# rev_p_2-v18.net
KiCad netlist of a schematic drawn in EAGLE
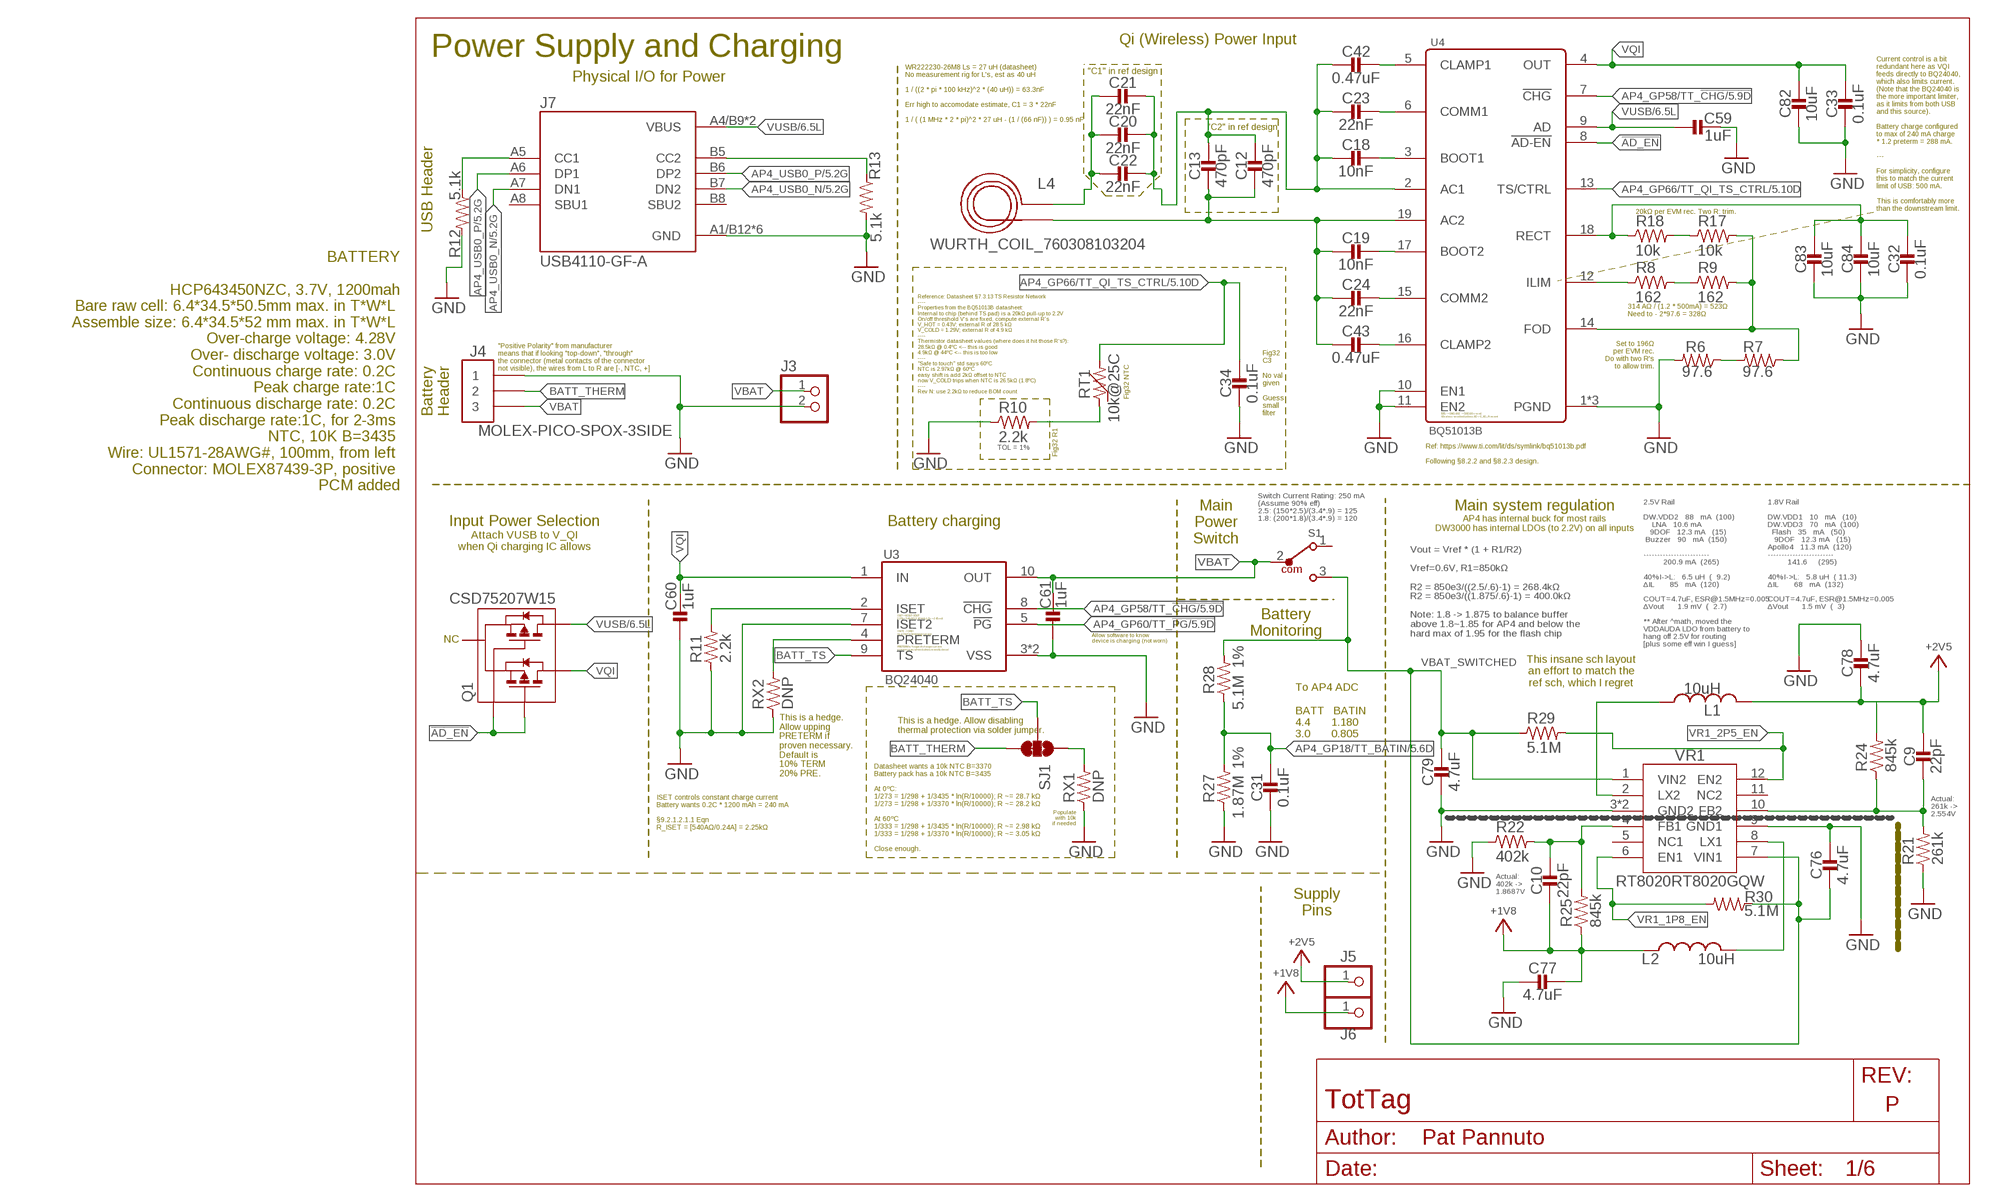
[diagram p0: schematic, sheet 1]
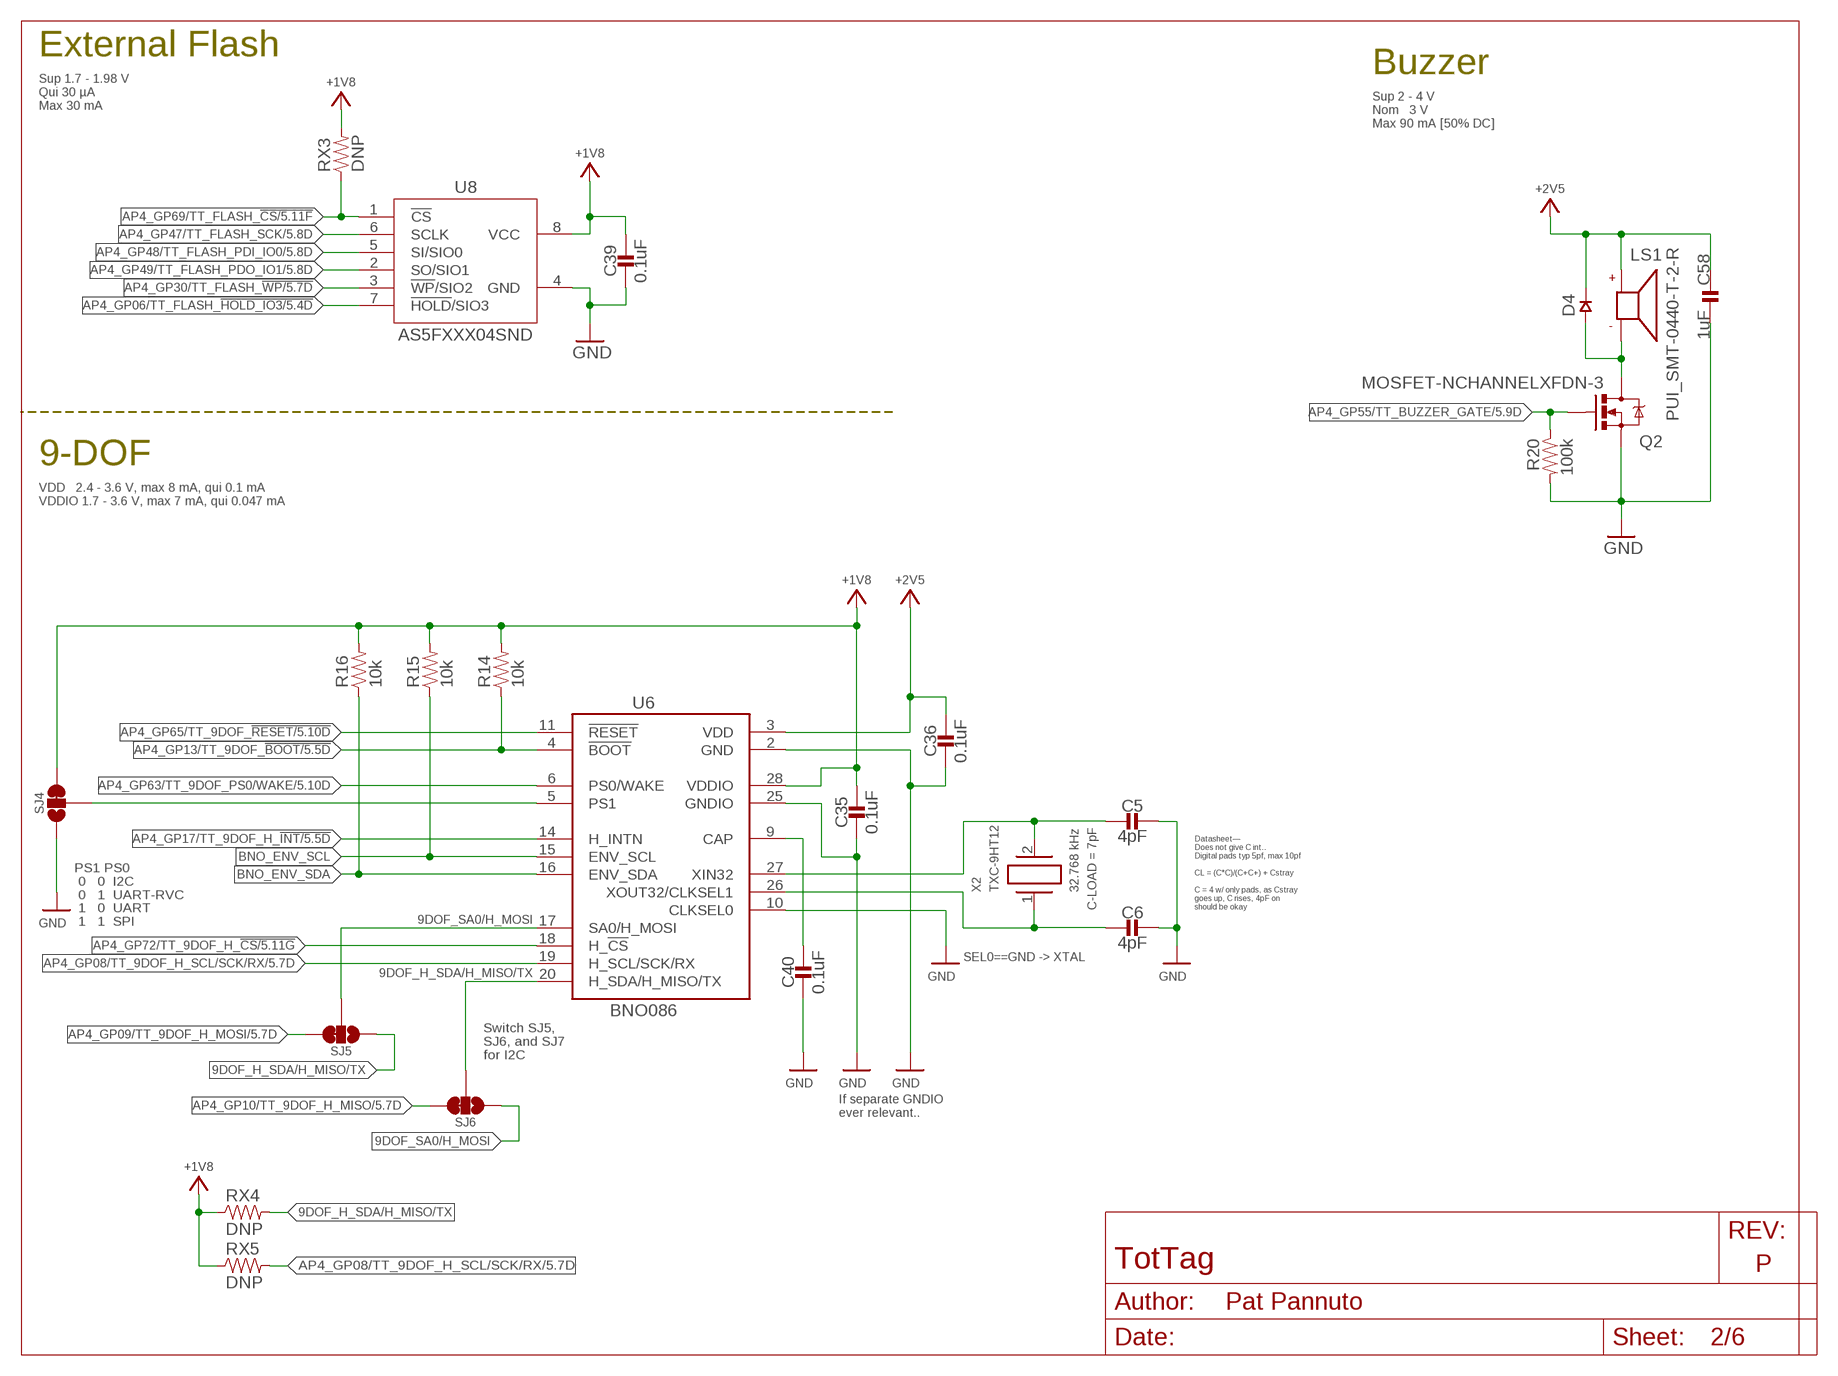
[diagram p1: schematic, sheet 2]
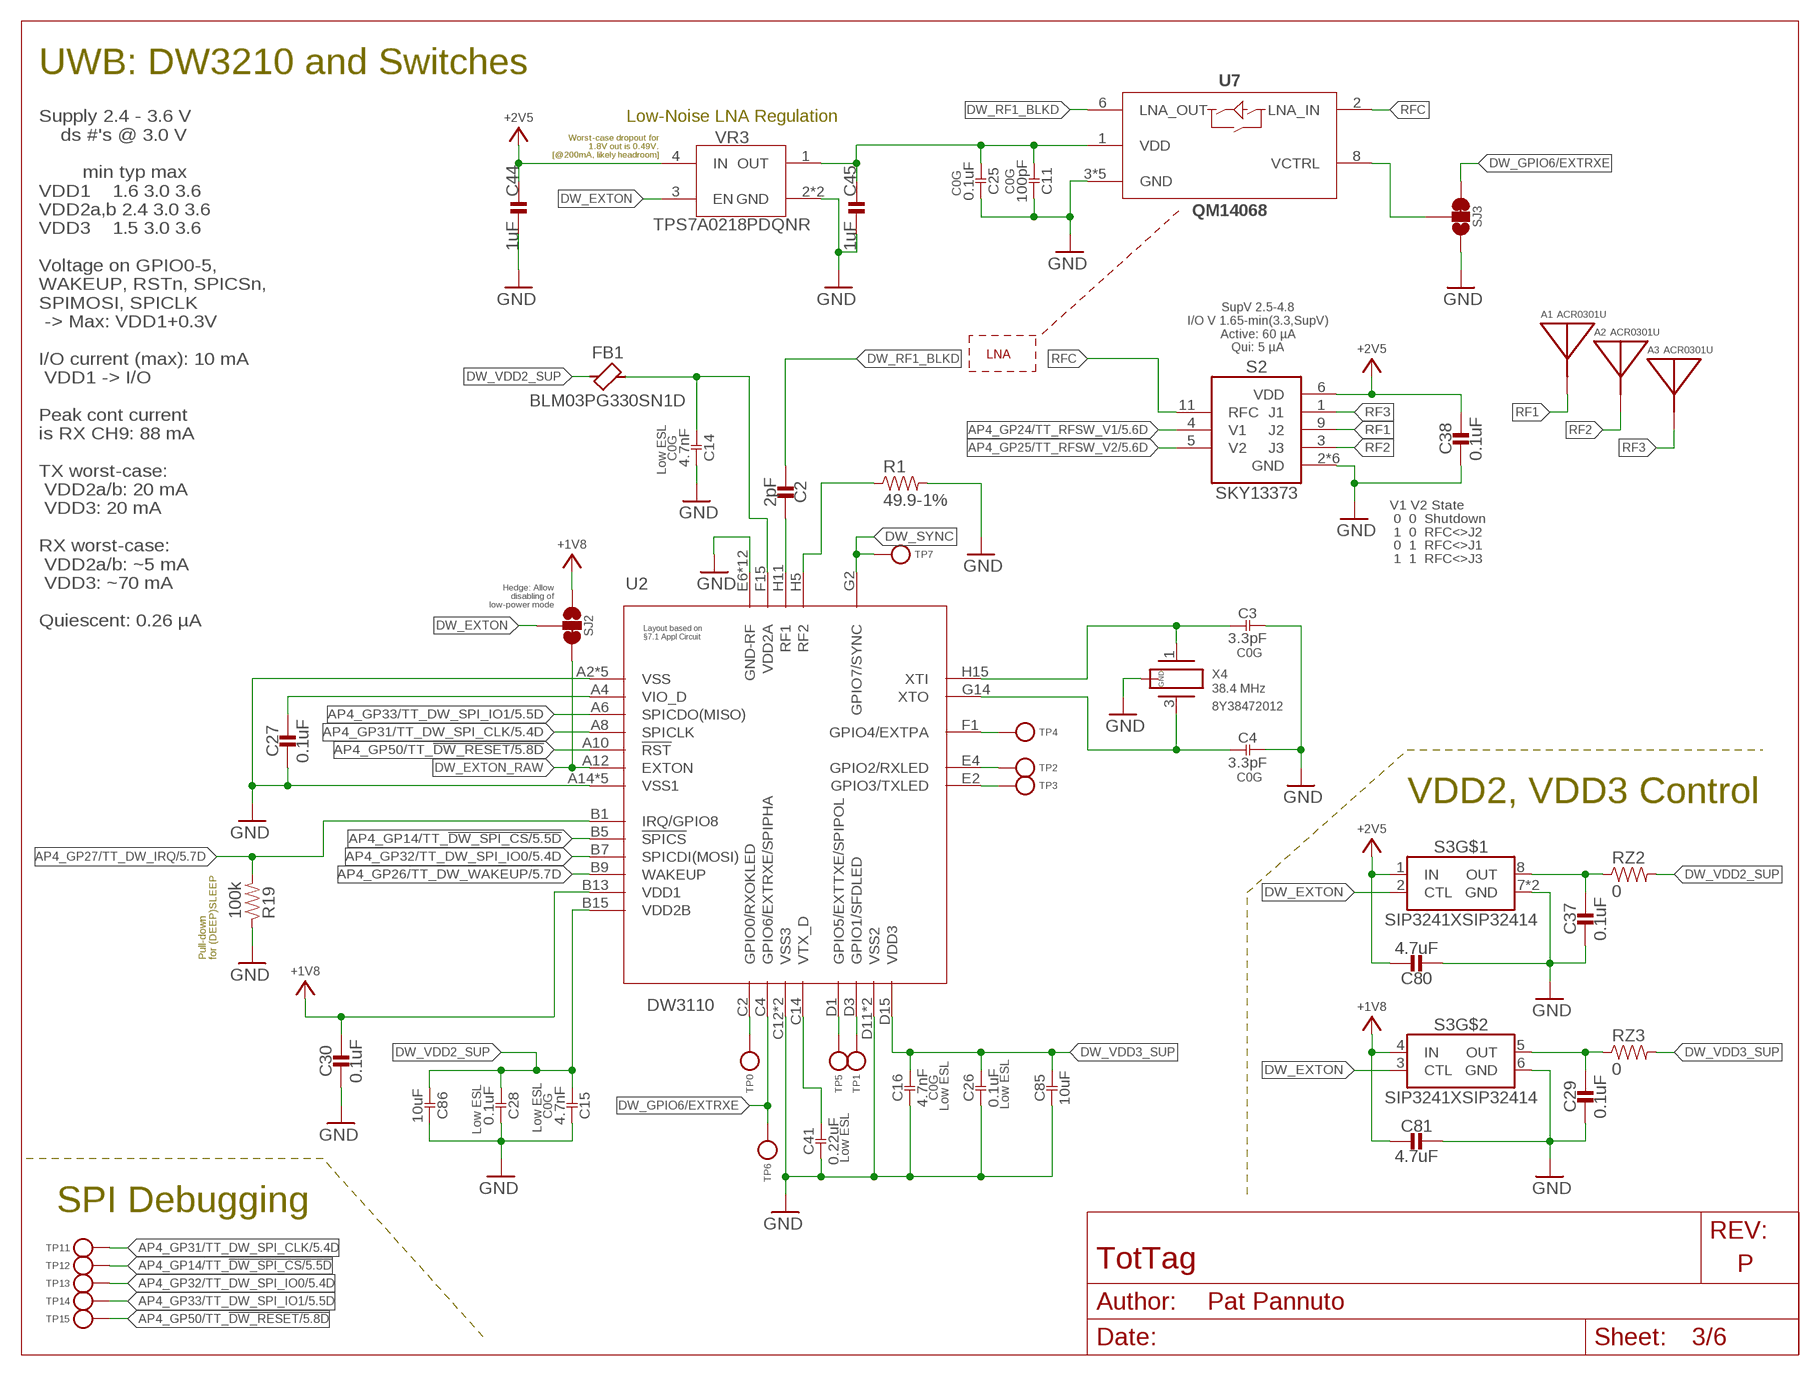
[diagram p2: schematic, sheet 3]
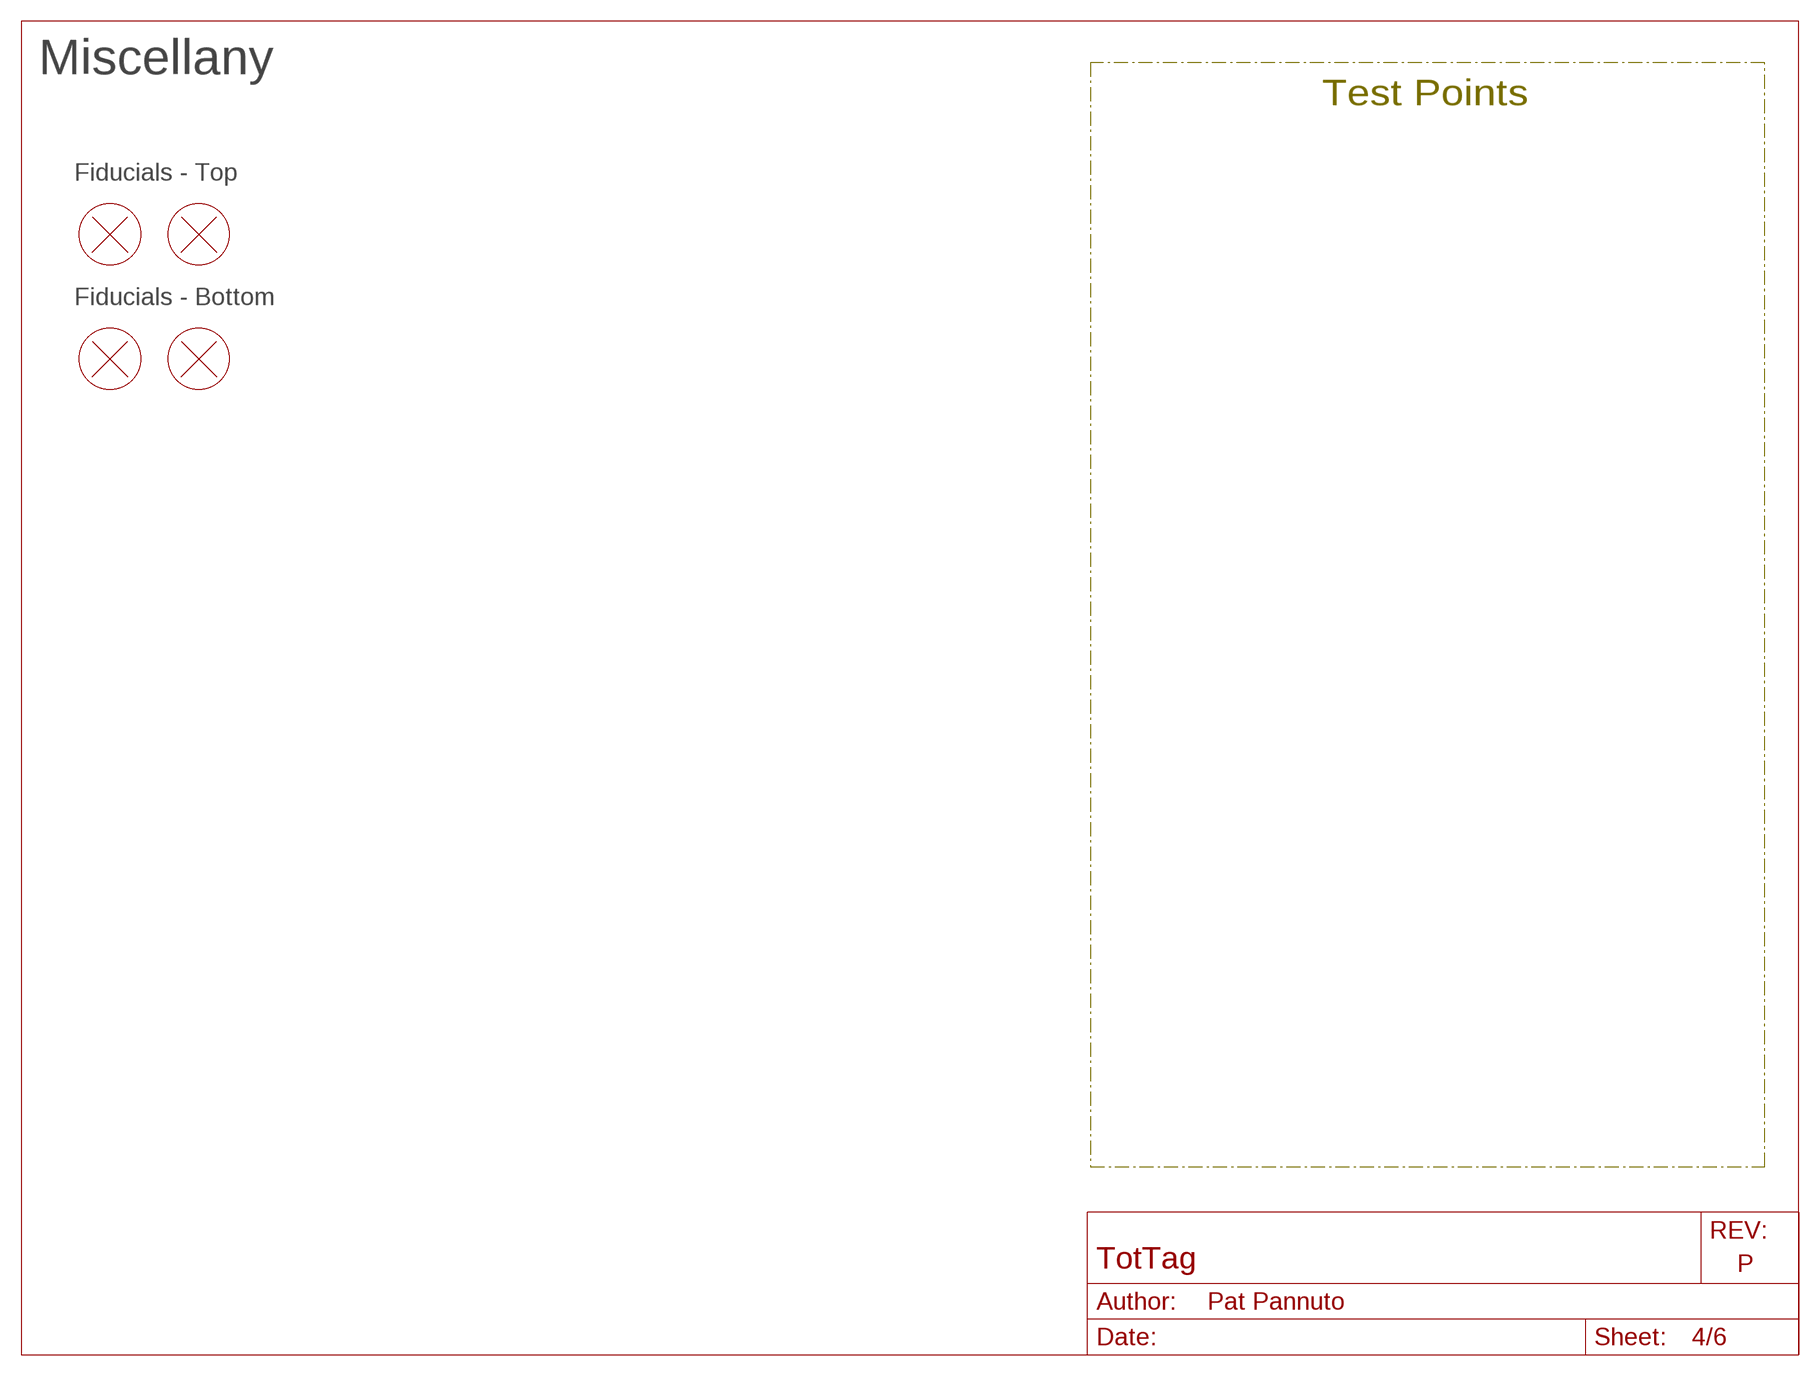
[diagram p3: schematic, sheet 4]
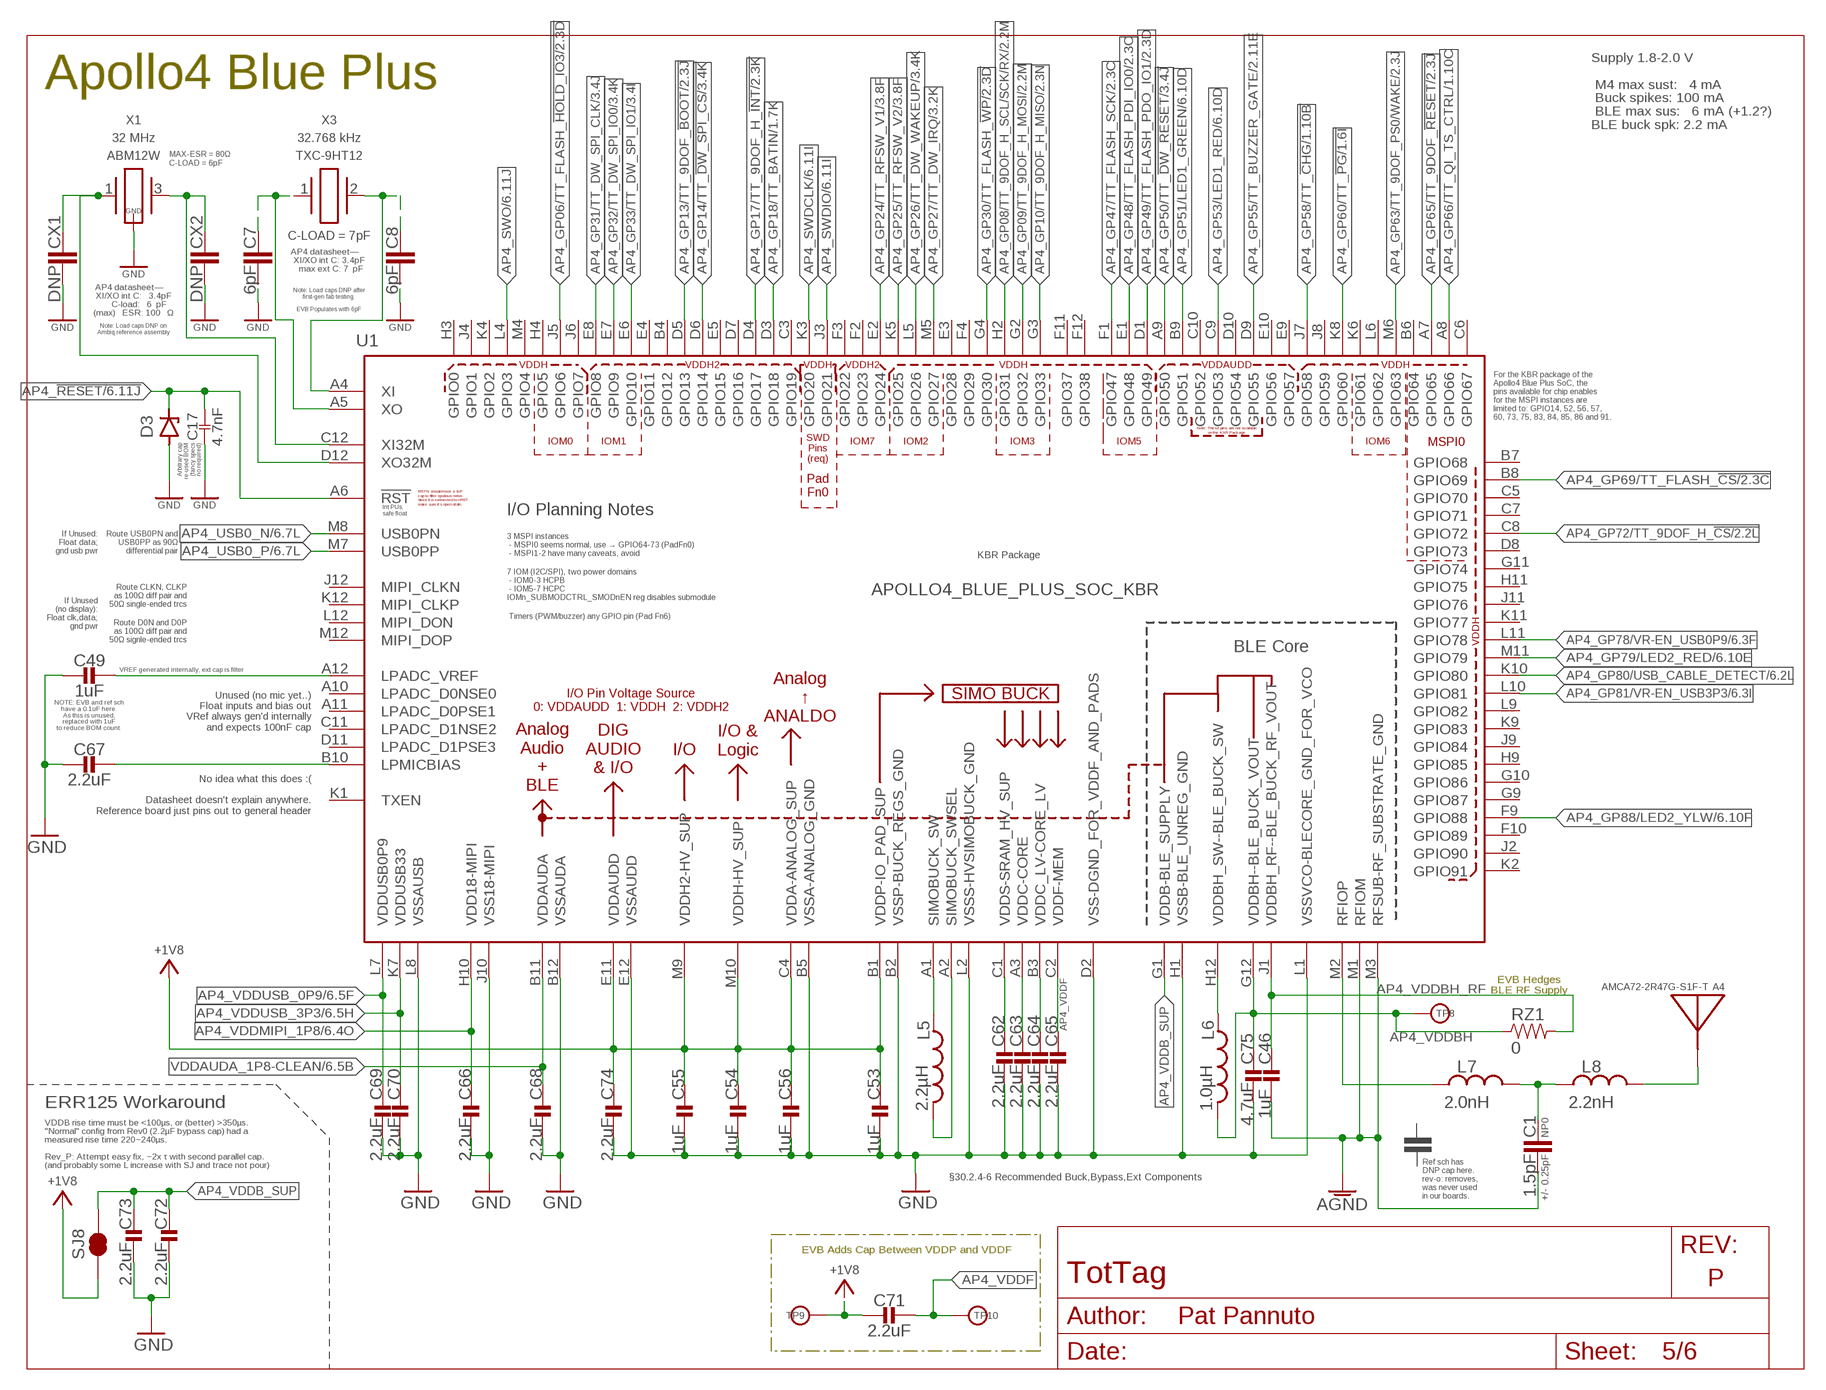
[diagram p4: schematic, sheet 5]
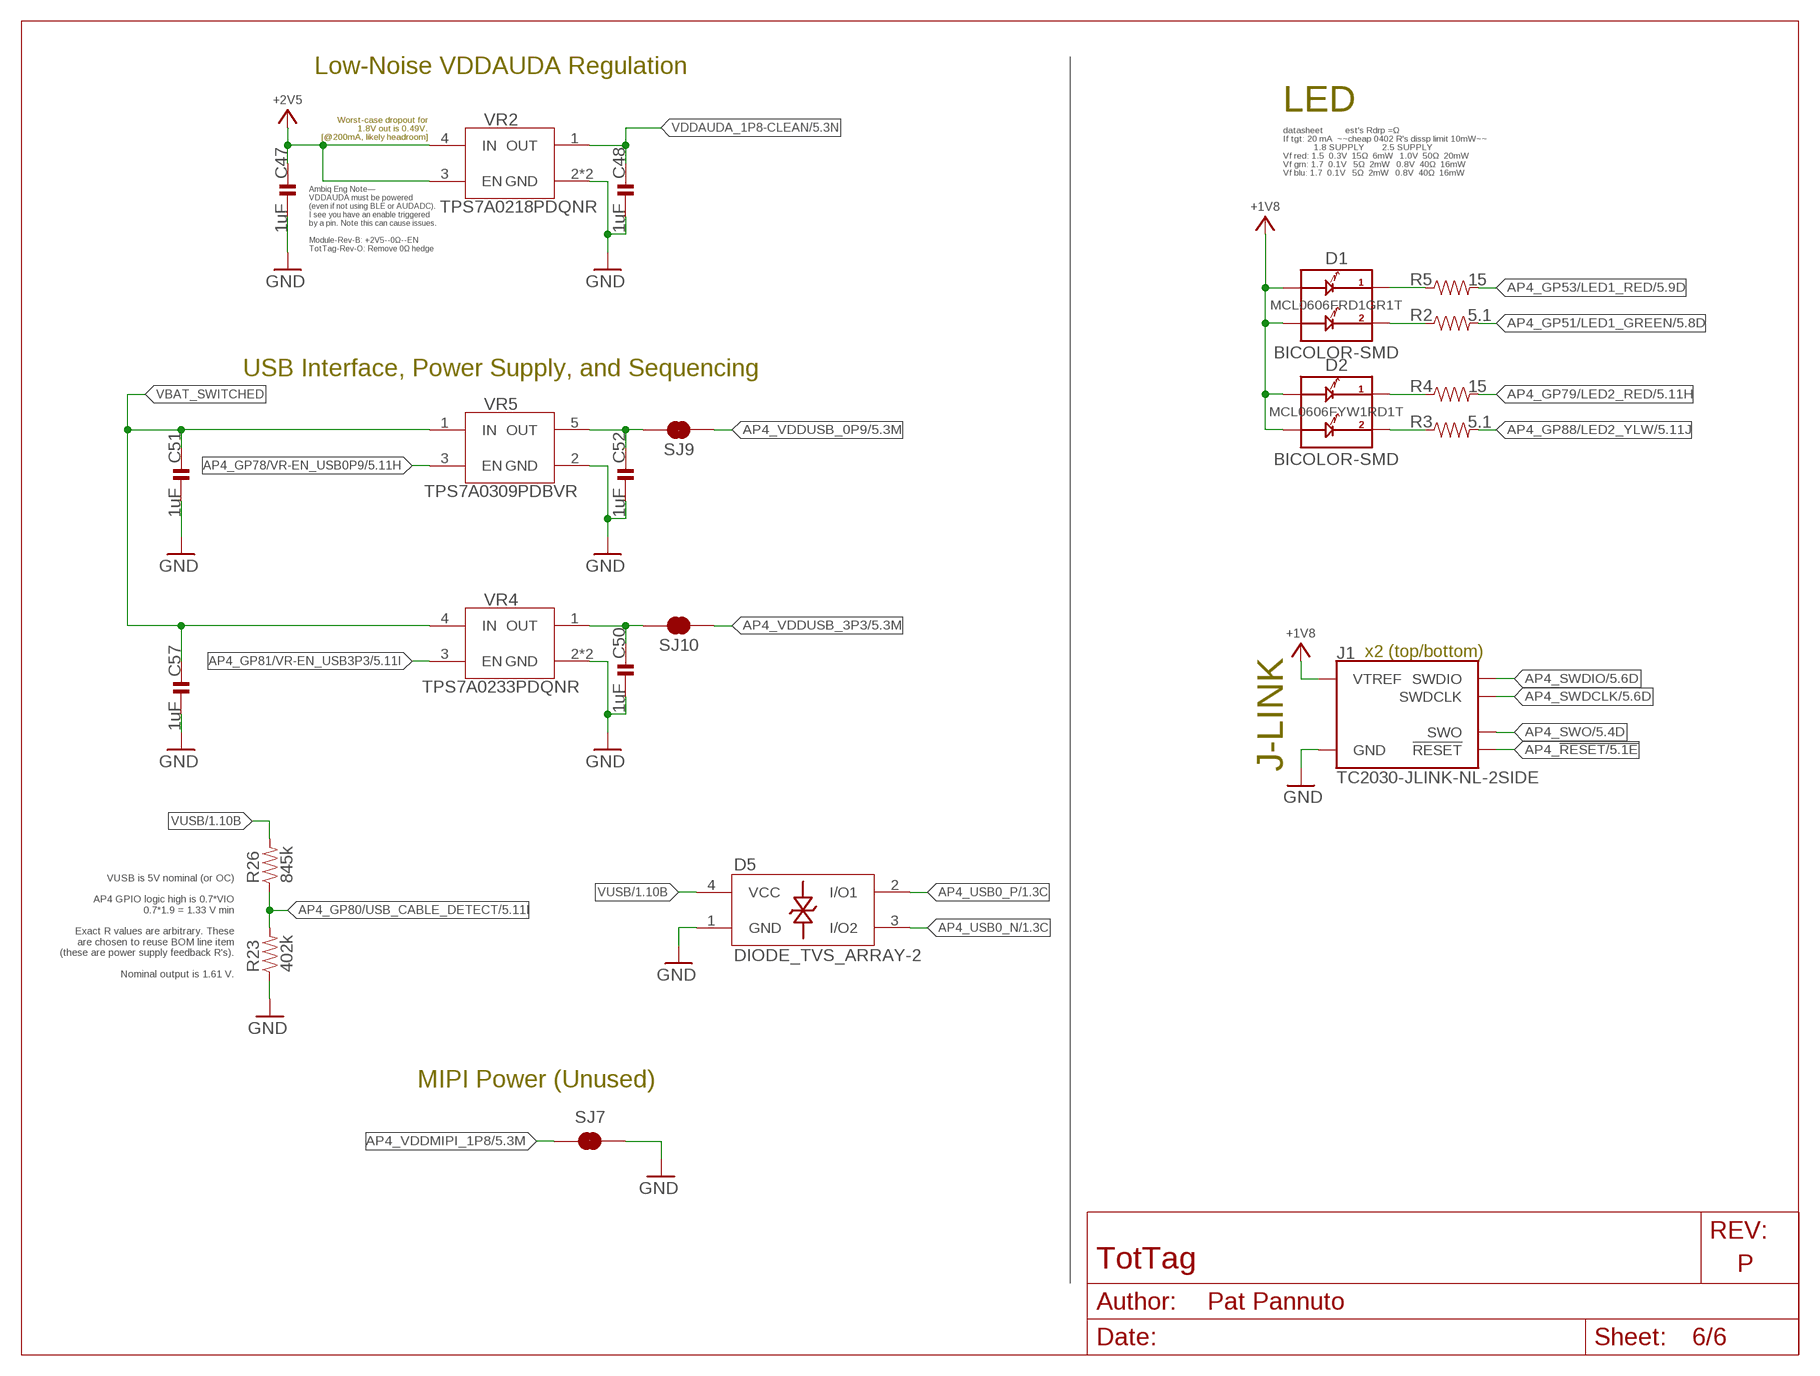
[diagram p5: schematic, sheet 6]

(export (version "E")
  (design (tool "Eeschema 10.0.6"))
  (components
    (comp (ref "C5")
      (value "4pF")
      (footprint "eagle-import:0201_CAP")
      (fields (field (name "MANUFACTURER") "Murata") (field (name "MPN") "GRM0335C1H4R0BA01D"))
      (libsource (lib "eagle-import") (part "passives_20904581_CAPACITOR0201_CAP"))
    )
    (comp (ref "C6")
      (value "4pF")
      (footprint "eagle-import:0201_CAP")
      (fields (field (name "MANUFACTURER") "Murata") (field (name "MPN") "GRM0335C1H4R0BA01D"))
      (libsource (lib "eagle-import") (part "passives_20904581_CAPACITOR0201_CAP"))
    )
    (comp (ref "C35")
      (value "0.1uF")
      (footprint "eagle-import:0402_CAP")
      (fields (field (name "MPN") "CL05A104KP5NNNC"))
      (libsource (lib "eagle-import") (part "passives_20904581_CAPACITOR0402_CAP"))
    )
    (comp (ref "C36")
      (value "0.1uF")
      (footprint "eagle-import:0402_CAP")
      (fields (field (name "MPN") "CL05A104KP5NNNC"))
      (libsource (lib "eagle-import") (part "passives_20904581_CAPACITOR0402_CAP"))
    )
    (comp (ref "C39")
      (value "0.1uF")
      (footprint "eagle-import:0402_CAP")
      (fields (field (name "MPN") "CL05A104KP5NNNC"))
      (libsource (lib "eagle-import") (part "passives_20904581_CAPACITOR0402_CAP"))
    )
    (comp (ref "C40")
      (value "0.1uF")
      (footprint "eagle-import:0402_CAP")
      (fields (field (name "MPN") "CL05A104KP5NNNC"))
      (libsource (lib "eagle-import") (part "CAPACITOR0402_CAP"))
    )
    (comp (ref "C58")
      (value "1uF")
      (footprint "eagle-import:0201_CAP")
      (fields (field (name "MANUFACTURER") "Murata") (field (name "MPN") "GRM033R61A105ME44D"))
      (libsource (lib "eagle-import") (part "passives_20904581_CAPACITOR0201_CAP"))
    )
    (comp (ref "D4")
      (value "DIODE0402")
      (footprint "eagle-import:0402_DIODE")
      (fields (field (name "MPN") "CDSQR400B-HF"))
      (libsource (lib "eagle-import") (part "DIODE0402"))
    )
    (comp (ref "LS1")
      (value "PUI_SMT-0440-T-2-R")
      (footprint "eagle-import:SMT-0440-T-2-R")
      (fields (field (name "MPN") "SMT-0440-T-2-R"))
      (libsource (lib "eagle-import") (part "PUI_SMT-0440-T-2-R"))
    )
    (comp (ref "Q2")
      (value "MOSFET-NCHANNELXFDN-3")
      (footprint "eagle-import:XFDFN-3")
      (libsource (lib "eagle-import") (part "MOSFET-NCHANNELXFDN-3"))
    )
    (comp (ref "R14")
      (value "10k")
      (footprint "eagle-import:0402_RES")
      (fields (field (name "MPN") "RC0402JR-0710KL"))
      (libsource (lib "eagle-import") (part "RESISTOR0402_RES"))
    )
    (comp (ref "R15")
      (value "10k")
      (footprint "eagle-import:0402_RES")
      (fields (field (name "MPN") "RC0402JR-0710KL"))
      (libsource (lib "eagle-import") (part "RESISTOR0402_RES"))
    )
    (comp (ref "R16")
      (value "10k")
      (footprint "eagle-import:0402_RES")
      (fields (field (name "MPN") "RC0402JR-0710KL"))
      (libsource (lib "eagle-import") (part "RESISTOR0402_RES"))
    )
    (comp (ref "R20")
      (value "100k")
      (footprint "eagle-import:0402_RES")
      (fields (field (name "MPN") "RT0402BRE07100KL"))
      (libsource (lib "eagle-import") (part "RESISTOR0402_RES"))
    )
    (comp (ref "RX3")
      (value "DNP")
      (footprint "eagle-import:0603-RES")
      (libsource (lib "eagle-import") (part "passives_20904581_RESISTOR0603_RES"))
    )
    (comp (ref "RX4")
      (value "DNP")
      (footprint "eagle-import:0603-RES")
      (libsource (lib "eagle-import") (part "passives_20904581_RESISTOR0603_RES"))
    )
    (comp (ref "RX5")
      (value "DNP")
      (footprint "eagle-import:0603-RES")
      (libsource (lib "eagle-import") (part "passives_20904581_RESISTOR0603_RES"))
    )
    (comp (ref "SJ4")
      (value "JUMPER-SMT_3_1-NC_TRACE_SILK")
      (footprint "eagle-import:SMT-JUMPER_3_1-NC_TRACE_SILK")
      (libsource (lib "eagle-import") (part "JUMPER-SMT_3_1-NC_TRACE_SILK"))
    )
    (comp (ref "SJ5")
      (value "JUMPER-SMT_3_1-NC_TRACE_SILK")
      (footprint "eagle-import:SMT-JUMPER_3_1-NC_TRACE_SILK")
      (libsource (lib "eagle-import") (part "JUMPER-SMT_3_1-NC_TRACE_SILK"))
    )
    (comp (ref "SJ6")
      (value "JUMPER-SMT_3_1-NC_TRACE_SILK")
      (footprint "eagle-import:SMT-JUMPER_3_1-NC_TRACE_SILK")
      (libsource (lib "eagle-import") (part "JUMPER-SMT_3_1-NC_TRACE_SILK"))
    )
    (comp (ref "U6")
      (value "BNO086")
      (footprint "eagle-import:LGA28R0P510X4_5P2X3P8X1")
      (fields (field (name "MANUFACTURER") "CEVA Technologies, Inc."))
      (libsource (lib "eagle-import") (part "BNO086"))
    )
    (comp (ref "U8")
      (value "AS5FXXX04SND")
      (footprint "eagle-import:AS5FXXXXXXXX-XXLXN")
      (fields (field (name "MANUFACTURER") "Alliance Memory") (field (name "MPN") "AS5F18G04SND-10LIN"))
      (libsource (lib "eagle-import") (part "AS5FXXX04SND"))
    )
    (comp (ref "X2")
      (value "TXC-9HT12")
      (footprint "eagle-import:TXC-9HT12")
      (fields
        (field (name "C-LOAD") "7pF")
        (field (name "FREQUENCY") "32.768 kHz")
        (field (name "MANUFACTURER") "TXC Corp")
        (field (name "MPN") "9HT12-32.768KDZY-T")
      )
      (libsource (lib "eagle-import") (part "TXC-9HT12"))
    )
    (comp (ref "A4")
      (value "AMCA72-2R47G-S1F-T")
      (footprint "eagle-import:AMCA72-2R470G-S1F-T")
      (fields (field (name "MPN") "AMCA72-2R470G-S1F-T4"))
      (libsource (lib "eagle-import") (part "AMCA72-2R47G-S1F-T"))
    )
    (comp (ref "C1")
      (value "1.5pF")
      (footprint "eagle-import:CAPC1005X60")
      (description "CAP CER 1.5PF 50V C0G/NP0 0402")
      (fields
        (field (name "MANUFACTURER") "KEMET")
        (field (name "MPN") "C0402C159C5GACTU")
        (field (name "TEMPCOEFF") "NP0")
        (field (name "TOLERANCE") "+/- 0.25pF")
      )
      (libsource (lib "eagle-import") (part "CCHIP-0402(1005-METRIC)_"))
    )
    (comp (ref "C7")
      (value "6pF")
      (footprint "eagle-import:CAPC1005X60")
      (fields (field (name "MANUFACTURER") "Murata") (field (name "MPN") "GCM1555C1H6R0BA16D"))
      (libsource (lib "eagle-import") (part "CCHIP-0402(1005-METRIC)_"))
    )
    (comp (ref "C8")
      (value "6pF")
      (footprint "eagle-import:CAPC1005X60")
      (fields (field (name "MANUFACTURER") "Murata") (field (name "MPN") "GCM1555C1H6R0BA16D"))
      (libsource (lib "eagle-import") (part "CCHIP-0402(1005-METRIC)_"))
    )
    (comp (ref "C17")
      (value "4.7nF")
      (footprint "eagle-import:SMD_1608M-0603US-C")
      (fields
        (field (name "EIA") "C0G")
        (field (name "FEATURES") "Low ESL")
        (field (name "MANUFACTURER") "KEMET")
        (field (name "MPN") "C0603C472J5GACTU")
      )
      (libsource (lib "eagle-import") (part "C0603US"))
    )
    (comp (ref "C46")
      (value "1uF")
      (footprint "eagle-import:0201_CAP")
      (fields (field (name "MANUFACTURER") "Murata") (field (name "MPN") "GRM033R61A105ME44D"))
      (libsource (lib "eagle-import") (part "passives_20904581_CAPACITOR0201_CAP"))
    )
    (comp (ref "C49")
      (value "1uF")
      (footprint "eagle-import:0201_CAP")
      (fields (field (name "MANUFACTURER") "MURATA") (field (name "MPN") "GRM033R61A105ME44D"))
      (libsource (lib "eagle-import") (part "passives_20904581_CAPACITOR0201_CAP"))
    )
    (comp (ref "C53")
      (value "1uF")
      (footprint "eagle-import:0201_CAP")
      (fields (field (name "MANUFACTURER") "Murata") (field (name "MPN") "GRM033R61A105ME44D"))
      (libsource (lib "eagle-import") (part "passives_20904581_CAPACITOR0201_CAP"))
    )
    (comp (ref "C54")
      (value "1uF")
      (footprint "eagle-import:0201_CAP")
      (fields (field (name "MANUFACTURER") "Murata") (field (name "MPN") "GRM033R61A105ME44D"))
      (libsource (lib "eagle-import") (part "passives_20904581_CAPACITOR0201_CAP"))
    )
    (comp (ref "C55")
      (value "1uF")
      (footprint "eagle-import:0201_CAP")
      (fields (field (name "MANUFACTURER") "Murata") (field (name "MPN") "GRM033R61A105ME44D"))
      (libsource (lib "eagle-import") (part "passives_20904581_CAPACITOR0201_CAP"))
    )
    (comp (ref "C56")
      (value "1uF")
      (footprint "eagle-import:0201_CAP")
      (fields (field (name "MANUFACTURER") "Murata") (field (name "MPN") "GRM033R61A105ME44D"))
      (libsource (lib "eagle-import") (part "passives_20904581_CAPACITOR0201_CAP"))
    )
    (comp (ref "C62")
      (value "2.2uF")
      (footprint "eagle-import:0201_CAP")
      (fields (field (name "MANUFACTURER") "Murata") (field (name "MPN") "GRM033R61A225KE47D"))
      (libsource (lib "eagle-import") (part "passives_20904581_CAPACITOR0201_CAP"))
    )
    (comp (ref "C63")
      (value "2.2uF")
      (footprint "eagle-import:0201_CAP")
      (fields (field (name "MANUFACTURER") "Murata") (field (name "MPN") "GRM033R61A225KE47D"))
      (libsource (lib "eagle-import") (part "passives_20904581_CAPACITOR0201_CAP"))
    )
    (comp (ref "C64")
      (value "2.2uF")
      (footprint "eagle-import:0201_CAP")
      (fields (field (name "MANUFACTURER") "Murata") (field (name "MPN") "GRM033R61A225KE47D"))
      (libsource (lib "eagle-import") (part "passives_20904581_CAPACITOR0201_CAP"))
    )
    (comp (ref "C65")
      (value "2.2uF")
      (footprint "eagle-import:0201_CAP")
      (fields (field (name "MANUFACTURER") "Murata") (field (name "MPN") "GRM033R61A225KE47D"))
      (libsource (lib "eagle-import") (part "passives_20904581_CAPACITOR0201_CAP"))
    )
    (comp (ref "C66")
      (value "2.2uF")
      (footprint "eagle-import:0201_CAP")
      (fields (field (name "MANUFACTURER") "Murata") (field (name "MPN") "GRM033R61A225KE47D"))
      (libsource (lib "eagle-import") (part "passives_20904581_CAPACITOR0201_CAP"))
    )
    (comp (ref "C67")
      (value "2.2uF")
      (footprint "eagle-import:0201_CAP")
      (fields (field (name "MANUFACTURER") "Murata") (field (name "MPN") "GRM033R61A225KE47D"))
      (libsource (lib "eagle-import") (part "passives_20904581_CAPACITOR0201_CAP"))
    )
    (comp (ref "C68")
      (value "2.2uF")
      (footprint "eagle-import:0201_CAP")
      (fields (field (name "MANUFACTURER") "Murata") (field (name "MPN") "GRM033R61A225KE47D"))
      (libsource (lib "eagle-import") (part "passives_20904581_CAPACITOR0201_CAP"))
    )
    (comp (ref "C69")
      (value "2.2uF")
      (footprint "eagle-import:0201_CAP")
      (fields (field (name "MANUFACTURER") "Murata") (field (name "MPN") "GRM033R61A225KE47D"))
      (libsource (lib "eagle-import") (part "passives_20904581_CAPACITOR0201_CAP"))
    )
    (comp (ref "C70")
      (value "2.2uF")
      (footprint "eagle-import:0201_CAP")
      (fields (field (name "MANUFACTURER") "Murata") (field (name "MPN") "GRM033R61A225KE47D"))
      (libsource (lib "eagle-import") (part "passives_20904581_CAPACITOR0201_CAP"))
    )
    (comp (ref "C71")
      (value "2.2uF")
      (footprint "eagle-import:0201_CAP")
      (fields (field (name "MANUFACTURER") "Murata") (field (name "MPN") "GRM033R61A225KE47D"))
      (libsource (lib "eagle-import") (part "passives_20904581_CAPACITOR0201_CAP"))
    )
    (comp (ref "C72")
      (value "2.2uF")
      (footprint "eagle-import:0201_CAP")
      (fields (field (name "MANUFACTURER") "Murata") (field (name "MPN") "GRM033R61A225KE47D"))
      (libsource (lib "eagle-import") (part "passives_20904581_CAPACITOR0201_CAP"))
    )
    (comp (ref "C73")
      (value "2.2uF")
      (footprint "eagle-import:0201_CAP")
      (fields (field (name "MANUFACTURER") "Murata") (field (name "MPN") "GRM033R61A225KE47D"))
      (libsource (lib "eagle-import") (part "passives_20904581_CAPACITOR0201_CAP"))
    )
    (comp (ref "C74")
      (value "2.2uF")
      (footprint "eagle-import:0201_CAP")
      (fields (field (name "MANUFACTURER") "Murata") (field (name "MPN") "GRM033R61A225KE47D"))
      (libsource (lib "eagle-import") (part "passives_20904581_CAPACITOR0201_CAP"))
    )
    (comp (ref "C75")
      (value "4.7uF")
      (footprint "eagle-import:0402_CAP")
      (fields (field (name "MPN") "CL05A475MP5NRNC"))
      (libsource (lib "eagle-import") (part "CAPACITOR0402_CAP"))
    )
    (comp (ref "CX1")
      (value "DNP")
      (footprint "eagle-import:CAPC1005X60")
      (libsource (lib "eagle-import") (part "CCHIP-0402(1005-METRIC)_"))
    )
    (comp (ref "CX2")
      (value "DNP")
      (footprint "eagle-import:CAPC1005X60")
      (libsource (lib "eagle-import") (part "CCHIP-0402(1005-METRIC)_"))
    )
    (comp (ref "D3")
      (value "ZENER")
      (footprint "eagle-import:SODFL1608X70")
      (description "DIODE TVS 5.5V STANDOFF 8V BREAKDOWN SC79")
      (fields (field (name "MANUFACTURER") "NXP SEMICONDUCTOR") (field (name "MPN") "PESD5V0X1UB,135"))
      (libsource (lib "eagle-import") (part "ZENERSODFL(1608-METRIC)_"))
    )
    (comp (ref "L5")
      (value "2.2µH")
      (footprint "eagle-import:0805_CAP")
      (fields (field (name "MANUFACTURER") "Murata") (field (name "MPN") "DFE201210U-2R2M=P2"))
      (libsource (lib "eagle-import") (part "INDUCTOR0805"))
    )
    (comp (ref "L6")
      (value "1.0µH")
      (footprint "eagle-import:0603_CAP")
      (fields (field (name "MANUFACTURER") "Taiyo Yuden") (field (name "MPN") "MCKK1608T1R0MN"))
      (libsource (lib "eagle-import") (part "INDUCTOR0603"))
    )
    (comp (ref "L7")
      (value "2.0nH")
      (footprint "eagle-import:INDC1006X60N")
      (description "FIXED IND 2.0NH0.1NH SMD")
      (fields
        (field (name "MANUFACTURER") "Murata")
        (field (name "MPN") "LQG15HS2N0B02D")
        (field (name "TOLERANCE") "+/- 0.1 nH")
      )
      (libsource (lib "eagle-import") (part "LCHIP-0402(1006-METRIC)_"))
    )
    (comp (ref "L8")
      (value "2.2nH")
      (footprint "eagle-import:INDC1006X60N")
      (description "FIXED IND 2.2NH0.1NH SMD")
      (fields
        (field (name "MANUFACTURER") "Murata")
        (field (name "MPN") "LQG15HN2N2B02D")
        (field (name "TOLERANCE") "+/- 0.1 nH")
      )
      (libsource (lib "eagle-import") (part "LCHIP-0402(1006-METRIC)_"))
    )
    (comp (ref "RZ1")
      (value "0")
      (footprint "eagle-import:0402_RES")
      (fields (field (name "MPN") "RMCF0402ZT0R00"))
      (libsource (lib "eagle-import") (part "passives_20904581_RESISTOR0402_RES"))
    )
    (comp (ref "SJ8")
      (value "JUMPER-SMT_2_NC_TRACE_SILK")
      (footprint "eagle-import:SMT-JUMPER_2_NC_TRACE_SILK")
      (libsource (lib "eagle-import") (part "JUMPER-SMT_2_NC_TRACE_SILK"))
    )
    (comp (ref "TP8")
      (value "TEST-POINT")
      (footprint "eagle-import:PAD.03X.03")
      (libsource (lib "eagle-import") (part "TEST-POINT"))
    )
    (comp (ref "TP9")
      (value "TEST-POINT")
      (footprint "eagle-import:PAD.03X.03")
      (libsource (lib "eagle-import") (part "TEST-POINT"))
    )
    (comp (ref "TP10")
      (value "TEST-POINT")
      (footprint "eagle-import:PAD.03X.03")
      (libsource (lib "eagle-import") (part "TEST-POINT"))
    )
    (comp (ref "U1")
      (value "APOLLO4_BLUE_PLUS_SOC_KBR")
      (footprint "eagle-import:APOLLO4_BLUE_SOC_BGA")
      (fields (field (name "MANUFACTURER") "Ambiq") (field (name "MPN") "AMA4B2KP-KBR"))
      (libsource (lib "eagle-import") (part "APOLLO4_BLUE_PLUS_SOC_KBR"))
    )
    (comp (ref "X1")
      (value "ABM12W")
      (footprint "eagle-import:ABM12W")
      (fields
        (field (name "C-LOAD") "6pF")
        (field (name "FREQUENCY") "32 MHz")
        (field (name "MANUFACTURER") "Abracon")
        (field (name "MAX-ESR") "80Ω")
        (field (name "MPN") "ABM12W-32.0000MHZ-6-D1X-T3")
      )
      (libsource (lib "eagle-import") (part "ABM12W"))
    )
    (comp (ref "X3")
      (value "TXC-9HT12")
      (footprint "eagle-import:TXC-9HT12")
      (fields
        (field (name "C-LOAD") "7pF")
        (field (name "FREQUENCY") "32.768 kHz")
        (field (name "MANUFACTURER") "TXC Corp")
        (field (name "MPN") "9HT12-32.768KDZY-T")
      )
      (libsource (lib "eagle-import") (part "TXC-9HT12"))
    )
    (comp (ref "C47")
      (value "1uF")
      (footprint "eagle-import:0201_CAP")
      (fields (field (name "MANUFACTURER") "Murata") (field (name "MPN") "GRM033R61A105ME44D"))
      (libsource (lib "eagle-import") (part "passives_20904581_CAPACITOR0201_CAP"))
    )
    (comp (ref "C48")
      (value "1uF")
      (footprint "eagle-import:0201_CAP")
      (fields (field (name "MANUFACTURER") "Murata") (field (name "MPN") "GRM033R61A105ME44D"))
      (libsource (lib "eagle-import") (part "passives_20904581_CAPACITOR0201_CAP"))
    )
    (comp (ref "C50")
      (value "1uF")
      (footprint "eagle-import:0201_CAP")
      (fields (field (name "MANUFACTURER") "Murata") (field (name "MPN") "GRM033R61A105ME44D"))
      (libsource (lib "eagle-import") (part "passives_20904581_CAPACITOR0201_CAP"))
    )
    (comp (ref "C51")
      (value "1uF")
      (footprint "eagle-import:0201_CAP")
      (fields (field (name "MANUFACTURER") "Murata") (field (name "MPN") "GRM033R61A105ME44D"))
      (libsource (lib "eagle-import") (part "passives_20904581_CAPACITOR0201_CAP"))
    )
    (comp (ref "C52")
      (value "1uF")
      (footprint "eagle-import:0201_CAP")
      (fields (field (name "MANUFACTURER") "Murata") (field (name "MPN") "GRM033R61A105ME44D"))
      (libsource (lib "eagle-import") (part "passives_20904581_CAPACITOR0201_CAP"))
    )
    (comp (ref "C57")
      (value "1uF")
      (footprint "eagle-import:0201_CAP")
      (fields (field (name "MANUFACTURER") "Murata") (field (name "MPN") "GRM033R61A105ME44D"))
      (libsource (lib "eagle-import") (part "passives_20904581_CAPACITOR0201_CAP"))
    )
    (comp (ref "D1")
      (value "BICOLOR-SMD")
      (footprint "eagle-import:LED-0606")
      (fields (field (name "MPN") "MCL0606FRD1GR1T"))
      (libsource (lib "eagle-import") (part "BICOLOR-SMD"))
    )
    (comp (ref "D2")
      (value "BICOLOR-SMD")
      (footprint "eagle-import:LED-0606")
      (fields (field (name "MPN") "MCL0606FYW1RD1T"))
      (libsource (lib "eagle-import") (part "BICOLOR-SMD"))
    )
    (comp (ref "D5")
      (value "DIODE_TVS_ARRAY-2")
      (footprint "eagle-import:SOT143B")
      (fields (field (name "MPN") "PRTR5V0U2X,215"))
      (libsource (lib "eagle-import") (part "DIODE_TVS_ARRAY-2"))
    )
    (comp (ref "J1")
      (value "TC2030-JLINK-NL-2SIDE")
      (footprint "eagle-import:TC2030-IDC-NL-2SIDE")
      (libsource (lib "eagle-import") (part "TC2030-JLINK-NL-2SIDE"))
    )
    (comp (ref "R2")
      (value "5.1")
      (footprint "eagle-import:0402_RES")
      (fields (field (name "MPN") "RC0402JR-075R1L"))
      (libsource (lib "eagle-import") (part "RESISTOR0402_RES"))
    )
    (comp (ref "R3")
      (value "5.1")
      (footprint "eagle-import:0402_RES")
      (fields (field (name "MPN") "RC0402JR-075R1L"))
      (libsource (lib "eagle-import") (part "RESISTOR0402_RES"))
    )
    (comp (ref "R4")
      (value "15")
      (footprint "eagle-import:0402_RES")
      (fields (field (name "MPN") "RC0402JR-0715RL"))
      (libsource (lib "eagle-import") (part "RESISTOR0402_RES"))
    )
    (comp (ref "R5")
      (value "15")
      (footprint "eagle-import:0402_RES")
      (fields (field (name "MPN") "RC0402JR-0715RL"))
      (libsource (lib "eagle-import") (part "RESISTOR0402_RES"))
    )
    (comp (ref "R23")
      (value "402k")
      (footprint "eagle-import:0201_RES")
      (fields (field (name "MPN") "ERJ-1GNF4023C"))
      (libsource (lib "eagle-import") (part "passives_20904581_RESISTOR0201_RES"))
    )
    (comp (ref "R26")
      (value "845k")
      (footprint "eagle-import:0201_RES")
      (fields (field (name "MPN") "ERJ-1GNF8453C"))
      (libsource (lib "eagle-import") (part "passives_20904581_RESISTOR0201_RES"))
    )
    (comp (ref "SJ7")
      (value "JUMPER-SMT_2_NC_TRACE_SILK")
      (footprint "eagle-import:SMT-JUMPER_2_NC_TRACE_SILK")
      (libsource (lib "eagle-import") (part "JUMPER-SMT_2_NC_TRACE_SILK"))
    )
    (comp (ref "SJ9")
      (value "JUMPER-SMT_2_NC_TRACE_SILK")
      (footprint "eagle-import:SMT-JUMPER_2_NC_TRACE_SILK")
      (libsource (lib "eagle-import") (part "JUMPER-SMT_2_NC_TRACE_SILK"))
    )
    (comp (ref "SJ10")
      (value "JUMPER-SMT_2_NC_TRACE_SILK")
      (footprint "eagle-import:SMT-JUMPER_2_NC_TRACE_SILK")
      (libsource (lib "eagle-import") (part "JUMPER-SMT_2_NC_TRACE_SILK"))
    )
    (comp (ref "VR2")
      (value "TPS7A0218PDQNR")
      (footprint "eagle-import:4-XDFN-EP")
      (libsource (lib "eagle-import") (part "TPS7A0218PDQNR"))
    )
    (comp (ref "VR4")
      (value "TPS7A0233PDQNR")
      (footprint "eagle-import:4-XDFN-EP")
      (libsource (lib "eagle-import") (part "TPS7A0233PDQNR"))
    )
    (comp (ref "VR5")
      (value "TPS7A0309PDBVR")
      (footprint "eagle-import:DBV0005A--SOT23-5-VARIANT")
      (libsource (lib "eagle-import") (part "TPS7A0309PDBVR"))
    )
    (comp (ref "FD1")
      (value "FIDUCIAL")
      (footprint "eagle-import:FIDUCIAL_1MM-CU_2MM-MASK")
      (libsource (lib "eagle-import") (part "FIDUCIAL"))
    )
    (comp (ref "FD2")
      (value "FIDUCIAL")
      (footprint "eagle-import:FIDUCIAL_1MM-CU_2MM-MASK")
      (libsource (lib "eagle-import") (part "FIDUCIAL"))
    )
    (comp (ref "FD3")
      (value "FIDUCIAL")
      (footprint "eagle-import:FIDUCIAL_1MM-CU_2MM-MASK")
      (libsource (lib "eagle-import") (part "FIDUCIAL"))
    )
    (comp (ref "FD4")
      (value "FIDUCIAL")
      (footprint "eagle-import:FIDUCIAL_1MM-CU_2MM-MASK")
      (libsource (lib "eagle-import") (part "FIDUCIAL"))
    )
    (comp (ref "C9")
      (value "22pF")
      (footprint "eagle-import:0201_CAP")
      (fields (field (name "MPN") "GRM0335C1H220FA01D"))
      (libsource (lib "eagle-import") (part "passives_20904581_CAPACITOR0201_CAP"))
    )
    (comp (ref "C10")
      (value "22pF")
      (footprint "eagle-import:0201_CAP")
      (fields (field (name "MPN") "GRM0335C1H220FA01D"))
      (libsource (lib "eagle-import") (part "passives_20904581_CAPACITOR0201_CAP"))
    )
    (comp (ref "C12")
      (value "470pF")
      (footprint "eagle-import:0402_CAP")
      (description "CAP CER 470PF 50V C0G/NP0 0402")
      (fields (field (name "MANUFACTURER") "Murata") (field (name "MPN") "GRM1555C1H471JA01J"))
      (libsource (lib "eagle-import") (part "passives_20904581_CAPACITOR0402_CAP"))
    )
    (comp (ref "C13")
      (value "470pF")
      (footprint "eagle-import:0402_CAP")
      (description "CAP CER 470PF 50V C0G/NP0 0402")
      (fields (field (name "MANUFACTURER") "Murata") (field (name "MPN") "GRM1555C1H471JA01J"))
      (libsource (lib "eagle-import") (part "passives_20904581_CAPACITOR0402_CAP"))
    )
    (comp (ref "C18")
      (value "10nF")
      (footprint "eagle-import:0402_CAP")
      (fields (field (name "MPN") "GRM155R71H103KA88J"))
      (libsource (lib "eagle-import") (part "passives_20904581_CAPACITOR0402_CAP"))
    )
    (comp (ref "C19")
      (value "10nF")
      (footprint "eagle-import:0402_CAP")
      (fields (field (name "MPN") "GRM155R71H103KA88J"))
      (libsource (lib "eagle-import") (part "passives_20904581_CAPACITOR0402_CAP"))
    )
    (comp (ref "C20")
      (value "22nF")
      (footprint "eagle-import:0402_CAP")
      (fields (field (name "MPN") "GRM155R71E223JA61D"))
      (libsource (lib "eagle-import") (part "passives_20904581_CAPACITOR0402_CAP"))
    )
    (comp (ref "C21")
      (value "22nF")
      (footprint "eagle-import:0402_CAP")
      (fields (field (name "MPN") "GRM155R71E223JA61D"))
      (libsource (lib "eagle-import") (part "passives_20904581_CAPACITOR0402_CAP"))
    )
    (comp (ref "C22")
      (value "22nF")
      (footprint "eagle-import:0402_CAP")
      (fields (field (name "MPN") "GRM155R71E223JA61D"))
      (libsource (lib "eagle-import") (part "passives_20904581_CAPACITOR0402_CAP"))
    )
    (comp (ref "C23")
      (value "22nF")
      (footprint "eagle-import:0402_CAP")
      (fields (field (name "MPN") "CC0402ZRY5V8BB223"))
      (libsource (lib "eagle-import") (part "passives_20904581_CAPACITOR0402_CAP"))
    )
    (comp (ref "C24")
      (value "22nF")
      (footprint "eagle-import:0402_CAP")
      (fields (field (name "MPN") "CC0402ZRY5V8BB223"))
      (libsource (lib "eagle-import") (part "passives_20904581_CAPACITOR0402_CAP"))
    )
    (comp (ref "C31")
      (value "0.1uF")
      (footprint "eagle-import:0402_CAP")
      (fields (field (name "MPN") "GRM155R71C104KA88J "))
      (libsource (lib "eagle-import") (part "CAPACITOR0402_CAP"))
    )
    (comp (ref "C32")
      (value "0.1uF")
      (footprint "eagle-import:0402_CAP")
      (fields (field (name "MPN") "GRM155R71C104KA88J "))
      (libsource (lib "eagle-import") (part "CAPACITOR0402_CAP"))
    )
    (comp (ref "C33")
      (value "0.1uF")
      (footprint "eagle-import:0402_CAP")
      (fields (field (name "MPN") "GRM155R71C104KA88J "))
      (libsource (lib "eagle-import") (part "CAPACITOR0402_CAP"))
    )
    (comp (ref "C34")
      (value "0.1uF")
      (footprint "eagle-import:0402_CAP")
      (fields (field (name "MPN") "GRM155R71C104KA88J "))
      (libsource (lib "eagle-import") (part "CAPACITOR0402_CAP"))
    )
    (comp (ref "C42")
      (value "0.47uF")
      (footprint "eagle-import:0402_CAP")
      (fields (field (name "MPN") "C1005X5R1E474K050BB"))
      (libsource (lib "eagle-import") (part "passives_20904581_CAPACITOR0402_CAP"))
    )
    (comp (ref "C43")
      (value "0.47uF")
      (footprint "eagle-import:0402_CAP")
      (fields (field (name "MPN") "C1005X5R1E474K050BB"))
      (libsource (lib "eagle-import") (part "passives_20904581_CAPACITOR0402_CAP"))
    )
    (comp (ref "C59")
      (value "1uF")
      (footprint "eagle-import:0201_CAP")
      (fields (field (name "MANUFACTURER") "Murata") (field (name "MPN") "GRM033R61A105ME44D"))
      (libsource (lib "eagle-import") (part "passives_20904581_CAPACITOR0201_CAP"))
    )
    (comp (ref "C60")
      (value "1uF")
      (footprint "eagle-import:0201_CAP")
      (fields (field (name "MANUFACTURER") "Murata") (field (name "MPN") "GRM033R61A105ME44D"))
      (libsource (lib "eagle-import") (part "passives_20904581_CAPACITOR0201_CAP"))
    )
    (comp (ref "C61")
      (value "1uF")
      (footprint "eagle-import:0201_CAP")
      (fields (field (name "MANUFACTURER") "Murata") (field (name "MPN") "GRM033R61A105ME44D"))
      (libsource (lib "eagle-import") (part "passives_20904581_CAPACITOR0201_CAP"))
    )
    (comp (ref "C76")
      (value "4.7uF")
      (footprint "eagle-import:0603_CAP")
      (fields (field (name "MPN") "C1608X7S1A475K080AC"))
      (libsource (lib "eagle-import") (part "passives_20904581_CAPACITOR0603_CAP"))
    )
    (comp (ref "C77")
      (value "4.7uF")
      (footprint "eagle-import:0603_CAP")
      (fields (field (name "MPN") "C1608X7S1A475K080AC"))
      (libsource (lib "eagle-import") (part "passives_20904581_CAPACITOR0603_CAP"))
    )
    (comp (ref "C78")
      (value "4.7uF")
      (footprint "eagle-import:0603_CAP")
      (fields (field (name "MPN") "C1608X7S1A475K080AC"))
      (libsource (lib "eagle-import") (part "passives_20904581_CAPACITOR0603_CAP"))
    )
    (comp (ref "C79")
      (value "4.7uF")
      (footprint "eagle-import:0603_CAP")
      (fields (field (name "MPN") "C1608X7S1A475K080AC"))
      (libsource (lib "eagle-import") (part "passives_20904581_CAPACITOR0603_CAP"))
    )
    (comp (ref "C82")
      (value "10uF")
      (footprint "eagle-import:0603_CAP")
      (fields (field (name "MPN") "CM105X5R106M25AT"))
      (libsource (lib "eagle-import") (part "passives_20904581_CAPACITOR0603_CAP"))
    )
    (comp (ref "C83")
      (value "10uF")
      (footprint "eagle-import:0603_CAP")
      (fields (field (name "MPN") "CM105X5R106M25AT"))
      (libsource (lib "eagle-import") (part "passives_20904581_CAPACITOR0603_CAP"))
    )
    (comp (ref "C84")
      (value "10uF")
      (footprint "eagle-import:0603_CAP")
      (fields (field (name "MPN") "CM105X5R106M25AT"))
      (libsource (lib "eagle-import") (part "passives_20904581_CAPACITOR0603_CAP"))
    )
    (comp (ref "J3")
      (value "PINHD-1X2")
      (footprint "eagle-import:1X02")
      (libsource (lib "eagle-import") (part "PINHD-1X2"))
    )
    (comp (ref "J4")
      (value "MOLEX-PICO-SPOX-3SIDE")
      (footprint "eagle-import:MOLEX-PICO-SPOX-3_SIDE")
      (libsource (lib "eagle-import") (part "MOLEX-PICO-SPOX-3SIDE"))
    )
    (comp (ref "J5")
      (value "PINHD-1X1")
      (footprint "eagle-import:1X01")
      (libsource (lib "eagle-import") (part "PINHD-1X1"))
    )
    (comp (ref "J6")
      (value "PINHD-1X1")
      (footprint "eagle-import:1X01")
      (libsource (lib "eagle-import") (part "PINHD-1X1"))
    )
    (comp (ref "J7")
      (value "USB4110-GF-A")
      (footprint "eagle-import:GCT_USB4110-GF-A")
      (fields (field (name "MF") "GCT"))
      (libsource (lib "eagle-import") (part "USB4110-GF-A"))
    )
    (comp (ref "L1")
      (value "10uH")
      (footprint "eagle-import:NRX3015")
      (fields (field (name "MANUFACTURER") "TAIYO YUDEN") (field (name "MPN") "NR3015T100M"))
      (libsource (lib "eagle-import") (part "INDUCTORNRX3015"))
    )
    (comp (ref "L2")
      (value "10uH")
      (footprint "eagle-import:NRX3015")
      (fields (field (name "MANUFACTURER") "TAIYO YUDEN") (field (name "MPN") "NR3015T100M"))
      (libsource (lib "eagle-import") (part "INDUCTORNRX3015"))
    )
    (comp (ref "L4")
      (value "WURTH_COIL_760308103204")
      (footprint "eagle-import:WURTH_COIL_760308103204")
      (fields (field (name "MANUFACTURER") "Würth Elektronik") (field (name "MPN") "760308103204"))
      (libsource (lib "eagle-import") (part "WURTH_COIL_760308103204"))
    )
    (comp (ref "Q1")
      (value "CSD75207W15")
      (footprint "eagle-import:DSBGA")
      (fields (field (name "MANUFACTURER") "TEXAS INSTRUMENTS"))
      (libsource (lib "eagle-import") (part "CSD75207W15"))
    )
    (comp (ref "R6")
      (value "97.6")
      (footprint "eagle-import:0402_RES")
      (fields (field (name "MPN") "RMCF0402FT97R6"))
      (libsource (lib "eagle-import") (part "passives_20904581_RESISTOR0402_RES"))
    )
    (comp (ref "R7")
      (value "97.6")
      (footprint "eagle-import:0402_RES")
      (fields (field (name "MPN") "RMCF0402FT97R6"))
      (libsource (lib "eagle-import") (part "passives_20904581_RESISTOR0402_RES"))
    )
    (comp (ref "R8")
      (value "162")
      (footprint "eagle-import:0402_RES")
      (fields (field (name "MPN") "RMCF0402FT162R"))
      (libsource (lib "eagle-import") (part "passives_20904581_RESISTOR0402_RES"))
    )
    (comp (ref "R9")
      (value "162")
      (footprint "eagle-import:0402_RES")
      (fields (field (name "MPN") "RMCF0402FT162R"))
      (libsource (lib "eagle-import") (part "passives_20904581_RESISTOR0402_RES"))
    )
    (comp (ref "R10")
      (value "2.2k")
      (footprint "eagle-import:0402_RES")
      (fields (field (name "MPN") "RC0402FR-072K2L") (field (name "TOL") "1%"))
      (libsource (lib "eagle-import") (part "RESISTOR0402_RES"))
    )
    (comp (ref "R11")
      (value "2.2k")
      (footprint "eagle-import:0402_RES")
      (fields (field (name "MPN") "RC0402FR-072K2L"))
      (libsource (lib "eagle-import") (part "passives_20904581_RESISTOR0402_RES"))
    )
    (comp (ref "R12")
      (value "5.1k")
      (footprint "eagle-import:0402_RES")
      (fields (field (name "MPN") "RMCF0402FT5K10"))
      (libsource (lib "eagle-import") (part "passives_20904581_RESISTOR0402_RES"))
    )
    (comp (ref "R13")
      (value "5.1k")
      (footprint "eagle-import:0402_RES")
      (fields (field (name "MPN") "RMCF0402FT5K10"))
      (libsource (lib "eagle-import") (part "passives_20904581_RESISTOR0402_RES"))
    )
    (comp (ref "R17")
      (value "10k")
      (footprint "eagle-import:0402_RES")
      (fields (field (name "MPN") "RC0402JR-0710KL"))
      (libsource (lib "eagle-import") (part "RESISTOR0402_RES"))
    )
    (comp (ref "R18")
      (value "10k")
      (footprint "eagle-import:0402_RES")
      (fields (field (name "MPN") "RC0402JR-0710KL"))
      (libsource (lib "eagle-import") (part "RESISTOR0402_RES"))
    )
    (comp (ref "R21")
      (value "261k")
      (footprint "eagle-import:0201_RES")
      (fields (field (name "MPN") "ERJ-1GNF2613C"))
      (libsource (lib "eagle-import") (part "passives_20904581_RESISTOR0201_RES"))
    )
    (comp (ref "R22")
      (value "402k")
      (footprint "eagle-import:0201_RES")
      (fields (field (name "MPN") "ERJ-1GNF4023C"))
      (libsource (lib "eagle-import") (part "passives_20904581_RESISTOR0201_RES"))
    )
    (comp (ref "R24")
      (value "845k")
      (footprint "eagle-import:0201_RES")
      (fields (field (name "MPN") "ERJ-1GNF8453C"))
      (libsource (lib "eagle-import") (part "passives_20904581_RESISTOR0201_RES"))
    )
    (comp (ref "R25")
      (value "845k")
      (footprint "eagle-import:0201_RES")
      (fields (field (name "MPN") "ERJ-1GNF8453C"))
      (libsource (lib "eagle-import") (part "passives_20904581_RESISTOR0201_RES"))
    )
    (comp (ref "R27")
      (value "1.87M")
      (footprint "eagle-import:0402_RES")
      (fields (field (name "MPN") "RMCF0402FT1M87") (field (name "TOLERANCE") "1%"))
      (libsource (lib "eagle-import") (part "RESISTOR0402_RES"))
    )
    (comp (ref "R28")
      (value "5.1M")
      (footprint "eagle-import:0402_RES")
      (fields (field (name "MPN") "RMCF0402FT5M10") (field (name "TOLERANCE") "1%"))
      (libsource (lib "eagle-import") (part "RESISTOR0402_RES"))
    )
    (comp (ref "R29")
      (value "5.1M")
      (footprint "eagle-import:0402_RES")
      (fields (field (name "MPN") "RMCF0402FT5M10"))
      (libsource (lib "eagle-import") (part "RESISTOR0402_RES"))
    )
    (comp (ref "R30")
      (value "5.1M")
      (footprint "eagle-import:0402_RES")
      (fields (field (name "MPN") "RMCF0402FT5M10"))
      (libsource (lib "eagle-import") (part "RESISTOR0402_RES"))
    )
    (comp (ref "RT1")
      (value "10k@25C")
      (footprint "eagle-import:0402_RES")
      (fields (field (name "MPN") "NCU15XH103F60RC"))
      (libsource (lib "eagle-import") (part "THERMISTOR0402"))
    )
    (comp (ref "RX1")
      (value "DNP")
      (footprint "eagle-import:0402_RES")
      (libsource (lib "eagle-import") (part "RESISTOR0402_RES"))
    )
    (comp (ref "RX2")
      (value "DNP")
      (footprint "eagle-import:0402_RES")
      (libsource (lib "eagle-import") (part "passives_20904581_RESISTOR0402_RES"))
    )
    (comp (ref "S1")
      (value "450404015514")
      (footprint "eagle-import:450404015514")
      (libsource (lib "eagle-import") (part "450404015514"))
    )
    (comp (ref "SJ1")
      (value "JUMPER-SMT_3_1-NC_TRACE_SILK")
      (footprint "eagle-import:SMT-JUMPER_3_1-NC_TRACE_SILK")
      (libsource (lib "eagle-import") (part "JUMPER-SMT_3_1-NC_TRACE_SILK"))
    )
    (comp (ref "U3")
      (value "BQ24040")
      (footprint "eagle-import:DSQ0010A")
      (fields (field (name "MPN") "BQ24040DSQR"))
      (libsource (lib "eagle-import") (part "BQ24040"))
    )
    (comp (ref "U4")
      (value "BQ51013B")
      (footprint "eagle-import:RHL0020A")
      (fields (field (name "MPN") "BQ51013BRHLR"))
      (libsource (lib "eagle-import") (part "BQ51013B"))
    )
    (comp (ref "VR1")
      (value "RT8020RT8020GQW")
      (footprint "eagle-import:SON45P300X300X80-13T160X250N")
      (fields (field (name "MANUFACTURER") "RichTek") (field (name "MPN") "RT8020GQW"))
      (libsource (lib "eagle-import") (part "RT8020RT8020GQW"))
    )
    (comp (ref "A1")
      (value "ACR0301U")
      (footprint "eagle-import:ACR0301U")
      (fields (field (name "MANUFACTURER") "Abracon"))
      (libsource (lib "eagle-import") (part "ACR0301U"))
    )
    (comp (ref "A2")
      (value "ACR0301U")
      (footprint "eagle-import:ACR0301U")
      (fields (field (name "MANUFACTURER") "Abracon"))
      (libsource (lib "eagle-import") (part "ACR0301U"))
    )
    (comp (ref "A3")
      (value "ACR0301U")
      (footprint "eagle-import:ACR0301U")
      (fields (field (name "MANUFACTURER") "Abracon"))
      (libsource (lib "eagle-import") (part "ACR0301U"))
    )
    (comp (ref "C2")
      (value "2pF")
      (footprint "eagle-import:0201_CAP")
      (fields (field (name "MPN") "CBR02C209A5GAC"))
      (libsource (lib "eagle-import") (part "CAPACITOR0201_CAP"))
    )
    (comp (ref "C3")
      (value "3.3pF")
      (footprint "eagle-import:SMD_2012M-0805US-C")
      (fields
        (field (name "EIA") "C0G")
        (field (name "MANUFACTURER") "KYOCERA AVX")
        (field (name "MPN") "600F3R3BT250XT")
      )
      (libsource (lib "eagle-import") (part "C0805US"))
    )
    (comp (ref "C4")
      (value "3.3pF")
      (footprint "eagle-import:SMD_2012M-0805US-C")
      (fields
        (field (name "EIA") "C0G")
        (field (name "MANUFACTURER") "KYOCERA AVX")
        (field (name "MPN") "600F3R3BT250XT")
      )
      (libsource (lib "eagle-import") (part "C0805US"))
    )
    (comp (ref "C11")
      (value "100pF")
      (footprint "eagle-import:SMD_1005M-0402US-C")
      (fields (field (name "EIA") "C0G") (field (name "MPN") "C0402C101J3GACTU"))
      (libsource (lib "eagle-import") (part "C0402US"))
    )
    (comp (ref "C14")
      (value "4.7nF")
      (footprint "eagle-import:SMD_1608M-0603US-C")
      (fields
        (field (name "EIA") "C0G")
        (field (name "FEATURES") "Low ESL")
        (field (name "MANUFACTURER") "KEMET")
        (field (name "MPN") "C0603C472J5GACTU")
      )
      (libsource (lib "eagle-import") (part "C0603US"))
    )
    (comp (ref "C15")
      (value "4.7nF")
      (footprint "eagle-import:SMD_1608M-0603US-C")
      (fields
        (field (name "EIA") "C0G")
        (field (name "FEATURES") "Low ESL")
        (field (name "MANUFACTURER") "KEMET")
        (field (name "MPN") "C0603C472J5GACTU")
      )
      (libsource (lib "eagle-import") (part "C0603US"))
    )
    (comp (ref "C16")
      (value "4.7nF")
      (footprint "eagle-import:SMD_1608M-0603US-C")
      (fields
        (field (name "EIA") "C0G")
        (field (name "FEATURES") "Low ESL")
        (field (name "MANUFACTURER") "KEMET")
        (field (name "MPN") "C0603C472J5GACTU")
      )
      (libsource (lib "eagle-import") (part "C0603US"))
    )
    (comp (ref "C25")
      (value "0.1uF")
      (footprint "eagle-import:SMD_3216M-1206US-C")
      (fields (field (name "EIA") "C0G") (field (name "MPN") "GRM31C5C1H104JA01L"))
      (libsource (lib "eagle-import") (part "C1206US"))
    )
    (comp (ref "C26")
      (value "0.1uF")
      (footprint "eagle-import:SMD_1608M-0603US-C")
      (fields (field (name "FEATURES") "Low ESL") (field (name "MPN") "C1608X7R1H104K080AA"))
      (libsource (lib "eagle-import") (part "C0603US"))
    )
    (comp (ref "C27")
      (value "0.1uF")
      (footprint "eagle-import:0402_CAP")
      (fields (field (name "MPN") "CL05A104KP5NNNC"))
      (libsource (lib "eagle-import") (part "passives_20904581_CAPACITOR0402_CAP"))
    )
    (comp (ref "C28")
      (value "0.1uF")
      (footprint "eagle-import:SMD_1608M-0603US-C")
      (fields (field (name "FEATURES") "Low ESL") (field (name "MPN") "C1608X7R1H104K080AA"))
      (libsource (lib "eagle-import") (part "C0603US"))
    )
    (comp (ref "C29")
      (value "0.1uF")
      (footprint "eagle-import:0402_CAP")
      (fields (field (name "MPN") "CL05A104KP5NNNC"))
      (libsource (lib "eagle-import") (part "passives_20904581_CAPACITOR0402_CAP"))
    )
    (comp (ref "C30")
      (value "0.1uF")
      (footprint "eagle-import:0402_CAP")
      (fields (field (name "MPN") "CL05A104KP5NNNC"))
      (libsource (lib "eagle-import") (part "passives_20904581_CAPACITOR0402_CAP"))
    )
    (comp (ref "C37")
      (value "0.1uF")
      (footprint "eagle-import:0402_CAP")
      (fields (field (name "MPN") "CL05A104KP5NNNC"))
      (libsource (lib "eagle-import") (part "passives_20904581_CAPACITOR0402_CAP"))
    )
    (comp (ref "C38")
      (value "0.1uF")
      (footprint "eagle-import:0402_CAP")
      (fields (field (name "MPN") "CL05A104KP5NNNC"))
      (libsource (lib "eagle-import") (part "passives_20904581_CAPACITOR0402_CAP"))
    )
    (comp (ref "C41")
      (value "0.22uF")
      (footprint "eagle-import:SMD_1608M-0603US-C")
      (fields (field (name "FEATURES") "Low ESL") (field (name "MPN") "C1608X7R1H224K080AB"))
      (libsource (lib "eagle-import") (part "C0603US"))
    )
    (comp (ref "C44")
      (value "1uF")
      (footprint "eagle-import:0201_CAP")
      (fields (field (name "MANUFACTURER") "Murata") (field (name "MPN") "GRM033R61A105ME44D"))
      (libsource (lib "eagle-import") (part "passives_20904581_CAPACITOR0201_CAP"))
    )
    (comp (ref "C45")
      (value "1uF")
      (footprint "eagle-import:0201_CAP")
      (fields (field (name "MANUFACTURER") "Murata") (field (name "MPN") "GRM033R61A105ME44D"))
      (libsource (lib "eagle-import") (part "passives_20904581_CAPACITOR0201_CAP"))
    )
    (comp (ref "C80")
      (value "4.7uF")
      (footprint "eagle-import:0603_CAP")
      (fields (field (name "MPN") "C1608X7S1A475K080AC"))
      (libsource (lib "eagle-import") (part "passives_20904581_CAPACITOR0603_CAP"))
    )
    (comp (ref "C81")
      (value "4.7uF")
      (footprint "eagle-import:0603_CAP")
      (fields (field (name "MPN") "C1608X7S1A475K080AC"))
      (libsource (lib "eagle-import") (part "passives_20904581_CAPACITOR0603_CAP"))
    )
    (comp (ref "C85")
      (value "10uF")
      (footprint "eagle-import:SMD_1608M-0603US-C")
      (fields (field (name "MPN") "CM105X5R106M25AT"))
      (libsource (lib "eagle-import") (part "C0603US"))
    )
    (comp (ref "C86")
      (value "10uF")
      (footprint "eagle-import:SMD_1608M-0603US-C")
      (fields (field (name "MPN") "CM105X5R106M25AT"))
      (libsource (lib "eagle-import") (part "C0603US"))
    )
    (comp (ref "FB1")
      (value "BLM03PG330SN1D")
      (footprint "eagle-import:0201_FB")
      (fields (field (name "MANUFACTURER") "Murata"))
      (libsource (lib "eagle-import") (part "FERRITE_BEAD0201"))
    )
    (comp (ref "R1")
      (value "49.9-1%")
      (footprint "eagle-import:0201_RES")
      (fields (field (name "MPN") "ERJ-1GNF49R9C"))
      (libsource (lib "eagle-import") (part "passives_20904581_RESISTOR0201_RES"))
    )
    (comp (ref "R19")
      (value "100k")
      (footprint "eagle-import:0402_RES")
      (fields (field (name "MPN") "RT0402BRE07100KL"))
      (libsource (lib "eagle-import") (part "RESISTOR0402_RES"))
    )
    (comp (ref "RZ2")
      (value "0")
      (footprint "eagle-import:0603-RES")
      (fields (field (name "MPN") "RMCF0603ZT0R00"))
      (libsource (lib "eagle-import") (part "passives_20904581_RESISTOR0603_RES"))
    )
    (comp (ref "RZ3")
      (value "0")
      (footprint "eagle-import:0603-RES")
      (fields (field (name "MPN") "RMCF0603ZT0R00"))
      (libsource (lib "eagle-import") (part "passives_20904581_RESISTOR0603_RES"))
    )
    (comp (ref "S2")
      (value "SKY13373")
      (footprint "eagle-import:SKY13373")
      (fields (field (name "MANUFACTURER") "Skyworks") (field (name "MPN") "SKY13373-460LF"))
      (libsource (lib "eagle-import") (part "SKY13373"))
    )
    (comp (ref "S3")
      (value "SIP3241XSIP32414")
      (footprint "eagle-import:TDFN2X2X0P6-8")
      (fields (field (name "MANUFACTURER") "Vishay") (field (name "MPN") "SIP32414DNP-T1-GE4"))
      (libsource (lib "eagle-import") (part "SIP3241XSIP32414"))
    )
    (comp (ref "SJ2")
      (value "JUMPER-SMT_3_1-NC_TRACE_SILK")
      (footprint "eagle-import:SMT-JUMPER_3_1-NC_TRACE_SILK")
      (libsource (lib "eagle-import") (part "JUMPER-SMT_3_1-NC_TRACE_SILK"))
    )
    (comp (ref "SJ3")
      (value "JUMPER-SMT_3_1-NC_TRACE_SILK")
      (footprint "eagle-import:SMT-JUMPER_3_1-NC_TRACE_SILK")
      (libsource (lib "eagle-import") (part "JUMPER-SMT_3_1-NC_TRACE_SILK"))
    )
    (comp (ref "TP0")
      (value "TEST-POINT")
      (footprint "eagle-import:PAD.03X.03")
      (libsource (lib "eagle-import") (part "TEST-POINT"))
    )
    (comp (ref "TP1")
      (value "TEST-POINT")
      (footprint "eagle-import:PAD.03X.03")
      (libsource (lib "eagle-import") (part "TEST-POINT"))
    )
    (comp (ref "TP2")
      (value "TEST-POINT")
      (footprint "eagle-import:PAD.03X.03")
      (libsource (lib "eagle-import") (part "TEST-POINT"))
    )
    (comp (ref "TP3")
      (value "TEST-POINT")
      (footprint "eagle-import:PAD.03X.03")
      (libsource (lib "eagle-import") (part "TEST-POINT"))
    )
    (comp (ref "TP4")
      (value "TEST-POINT")
      (footprint "eagle-import:PAD.03X.03")
      (libsource (lib "eagle-import") (part "TEST-POINT"))
    )
    (comp (ref "TP5")
      (value "TEST-POINT")
      (footprint "eagle-import:PAD.03X.03")
      (libsource (lib "eagle-import") (part "TEST-POINT"))
    )
    (comp (ref "TP6")
      (value "TEST-POINT")
      (footprint "eagle-import:PAD.03X.03")
      (libsource (lib "eagle-import") (part "TEST-POINT"))
    )
    (comp (ref "TP7")
      (value "TEST-POINT")
      (footprint "eagle-import:PAD.03X.03")
      (libsource (lib "eagle-import") (part "TEST-POINT"))
    )
    (comp (ref "TP11")
      (value "TEST-POINT")
      (footprint "eagle-import:PAD.03X.03")
      (libsource (lib "eagle-import") (part "TEST-POINT"))
    )
    (comp (ref "TP12")
      (value "TEST-POINT")
      (footprint "eagle-import:PAD.03X.03")
      (libsource (lib "eagle-import") (part "TEST-POINT"))
    )
    (comp (ref "TP13")
      (value "TEST-POINT")
      (footprint "eagle-import:PAD.03X.03")
      (libsource (lib "eagle-import") (part "TEST-POINT"))
    )
    (comp (ref "TP14")
      (value "TEST-POINT")
      (footprint "eagle-import:PAD.03X.03")
      (libsource (lib "eagle-import") (part "TEST-POINT"))
    )
    (comp (ref "TP15")
      (value "TEST-POINT")
      (footprint "eagle-import:PAD.03X.03")
      (libsource (lib "eagle-import") (part "TEST-POINT"))
    )
    (comp (ref "U2")
      (value "DW3110")
      (footprint "eagle-import:WLCSP52")
      (fields (field (name "MANUFACTURER") "Qorvo"))
      (libsource (lib "eagle-import") (part "DW3110"))
    )
    (comp (ref "U7")
      (value "QM14068")
      (footprint "eagle-import:QM14068")
      (fields (field (name "MANUFACTURER") "Qorvo"))
      (libsource (lib "eagle-import") (part "QM14068"))
    )
    (comp (ref "VR3")
      (value "TPS7A0218PDQNR")
      (footprint "eagle-import:4-XDFN-EP")
      (libsource (lib "eagle-import") (part "TPS7A0218PDQNR"))
    )
    (comp (ref "X4")
      (value "TXC-8Y")
      (footprint "eagle-import:TXC-8Y")
      (fields
        (field (name "FREQ") "38.4 MHz")
        (field (name "MANUFACTURER") "TXC")
        (field (name "MPN") "8Y38472012")
      )
      (libsource (lib "eagle-import") (part "TXC-8Y"))
    )
  )
  (nets
    (net (code "1") (name "+1V8") (class "Default")
      (node (ref "C10") (pin "P$2") (pinfunction "2_P$2") (pintype "bidirectional"))
      (node (ref "C30") (pin "1") (pinfunction "1_1") (pintype "bidirectional"))
      (node (ref "C35") (pin "1") (pinfunction "1_1") (pintype "bidirectional"))
      (node (ref "C39") (pin "1") (pinfunction "1_1") (pintype "bidirectional"))
      (node (ref "C53") (pin "P$1") (pinfunction "1_P$1") (pintype "bidirectional"))
      (node (ref "C54") (pin "P$1") (pinfunction "1_P$1") (pintype "bidirectional"))
      (node (ref "C55") (pin "P$1") (pinfunction "1_P$1") (pintype "bidirectional"))
      (node (ref "C56") (pin "P$1") (pinfunction "1_P$1") (pintype "bidirectional"))
      (node (ref "C71") (pin "P$2") (pinfunction "2_P$2") (pintype "bidirectional"))
      (node (ref "C74") (pin "P$1") (pinfunction "1_P$1") (pintype "bidirectional"))
      (node (ref "C77") (pin "1") (pinfunction "1_1") (pintype "bidirectional"))
      (node (ref "C81") (pin "2") (pinfunction "2_2") (pintype "bidirectional"))
      (node (ref "D1") (pin "A1") (pinfunction "A1_A1") (pintype "bidirectional"))
      (node (ref "D1") (pin "A2") (pinfunction "A2_A2") (pintype "bidirectional"))
      (node (ref "D2") (pin "A1") (pinfunction "A1_A1") (pintype "bidirectional"))
      (node (ref "D2") (pin "A2") (pinfunction "A2_A2") (pintype "bidirectional"))
      (node (ref "J1") (pin "1") (pinfunction "VTREF_1") (pintype "bidirectional"))
      (node (ref "J1") (pin "B1") (pinfunction "VTREF_B1") (pintype "bidirectional"))
      (node (ref "J6") (pin "1") (pinfunction "1_1") (pintype "passive"))
      (node (ref "L2") (pin "P$1") (pinfunction "1_P$1") (pintype "bidirectional"))
      (node (ref "R14") (pin "2") (pinfunction "2_2") (pintype "passive"))
      (node (ref "R15") (pin "2") (pinfunction "2_2") (pintype "passive"))
      (node (ref "R16") (pin "2") (pinfunction "2_2") (pintype "passive"))
      (node (ref "R25") (pin "1") (pinfunction "1_1") (pintype "passive"))
      (node (ref "RX3") (pin "2") (pinfunction "2_2") (pintype "passive"))
      (node (ref "RX4") (pin "1") (pinfunction "1_1") (pintype "passive"))
      (node (ref "RX5") (pin "1") (pinfunction "1_1") (pintype "passive"))
      (node (ref "S3") (pin "4") (pinfunction "IN_4") (pintype "bidirectional"))
      (node (ref "SJ2") (pin "1") (pinfunction "1_1") (pintype "passive"))
      (node (ref "SJ4") (pin "3") (pinfunction "3_3") (pintype "passive"))
      (node (ref "SJ8") (pin "1") (pinfunction "1_1") (pintype "passive"))
      (node (ref "TP9") (pin "P$1") (pinfunction "TESTPOINT_P$1") (pintype "bidirectional"))
      (node (ref "U1") (pin "B1") (pinfunction "VDDP-IO_PAD_SUP_B1") (pintype "bidirectional"))
      (node (ref "U1") (pin "C4") (pinfunction "VDDA-ANALOG_SUP_C4") (pintype "bidirectional"))
      (node (ref "U1") (pin "E11") (pinfunction "VDDAUDD_E11") (pintype "bidirectional"))
      (node (ref "U1") (pin "M10") (pinfunction "VDDH-HV_SUP_M10") (pintype "bidirectional"))
      (node (ref "U1") (pin "M9") (pinfunction "VDDH2-HV_SUP_M9") (pintype "bidirectional"))
      (node (ref "U2") (pin "B13") (pinfunction "VDD1_B13") (pintype "bidirectional"))
      (node (ref "U6") (pin "28") (pinfunction "VDDIO_28") (pintype "input"))
      (node (ref "U8") (pin "8") (pinfunction "VCC_8") (pintype "bidirectional"))
    )
    (net (code "2") (name "+2V5") (class "Default")
      (node (ref "C36") (pin "1") (pinfunction "1_1") (pintype "bidirectional"))
      (node (ref "C38") (pin "1") (pinfunction "1_1") (pintype "bidirectional"))
      (node (ref "C44") (pin "P$1") (pinfunction "1_P$1") (pintype "bidirectional"))
      (node (ref "C47") (pin "P$1") (pinfunction "1_P$1") (pintype "bidirectional"))
      (node (ref "C58") (pin "P$1") (pinfunction "1_P$1") (pintype "bidirectional"))
      (node (ref "C78") (pin "2") (pinfunction "2_2") (pintype "bidirectional"))
      (node (ref "C80") (pin "1") (pinfunction "1_1") (pintype "bidirectional"))
      (node (ref "C9") (pin "P$1") (pinfunction "1_P$1") (pintype "bidirectional"))
      (node (ref "D4") (pin "CATHODE") (pinfunction "CATHODE_CATHODE") (pintype "bidirectional"))
      (node (ref "J5") (pin "1") (pinfunction "1_1") (pintype "passive"))
      (node (ref "L1") (pin "P$2") (pinfunction "2_P$2") (pintype "bidirectional"))
      (node (ref "LS1") (pin "+") (pinfunction "P_+") (pintype "passive"))
      (node (ref "R24") (pin "2") (pinfunction "2_2") (pintype "passive"))
      (node (ref "S2") (pin "6") (pinfunction "VDD_6") (pintype "power_in"))
      (node (ref "S3") (pin "1") (pinfunction "IN_1") (pintype "bidirectional"))
      (node (ref "U6") (pin "3") (pinfunction "VDD_3") (pintype "input"))
      (node (ref "VR2") (pin "3") (pinfunction "EN_3") (pintype "input"))
      (node (ref "VR2") (pin "4") (pinfunction "IN_4") (pintype "bidirectional"))
      (node (ref "VR3") (pin "4") (pinfunction "IN_4") (pintype "bidirectional"))
    )
    (net (code "3") (name "9DOF_H_SDA{slash}H_MISO{slash}TX") (class "Default")
      (node (ref "RX4") (pin "2") (pinfunction "2_2") (pintype "passive"))
      (node (ref "SJ5") (pin "1") (pinfunction "1_1") (pintype "passive"))
      (node (ref "SJ6") (pin "2") (pinfunction "2_2") (pintype "passive"))
      (node (ref "U6") (pin "20") (pinfunction "H_SDA/H_MISO/TX_20") (pintype "bidirectional"))
    )
    (net (code "4") (name "9DOF_SA0{slash}H_MOSI") (class "Default")
      (node (ref "SJ5") (pin "2") (pinfunction "2_2") (pintype "passive"))
      (node (ref "SJ6") (pin "1") (pinfunction "1_1") (pintype "passive"))
      (node (ref "U6") (pin "17") (pinfunction "SA0/H_MOSI_17") (pintype "input"))
    )
    (net (code "5") (name "AGND") (class "Default")
      (node (ref "C1") (pin "2") (pinfunction "2_2") (pintype "passive"))
      (node (ref "C46") (pin "P$2") (pinfunction "2_P$2") (pintype "bidirectional"))
      (node (ref "U1") (pin "M1") (pinfunction "RFIOM_M1") (pintype "bidirectional"))
      (node (ref "U1") (pin "M3") (pinfunction "RFSUB-RF_SUBSTRATE_GND_M3") (pintype "bidirectional"))
    )
    (net (code "6") (name "AP4_GP06{slash}TT_FLASH_~{HOLD_IO3}") (class "Default")
      (node (ref "U1") (pin "J5") (pinfunction "GPIO6_J5") (pintype "bidirectional"))
      (node (ref "U8") (pin "7") (pinfunction "~{HOLD}/SIO3_7") (pintype "bidirectional"))
    )
    (net (code "7") (name "AP4_GP08{slash}TT_9DOF_H_SCL{slash}SCK{slash}RX") (class "Default")
      (node (ref "RX5") (pin "2") (pinfunction "2_2") (pintype "passive"))
      (node (ref "U1") (pin "H2") (pinfunction "GPIO31_H2") (pintype "bidirectional"))
      (node (ref "U6") (pin "19") (pinfunction "H_SCL/SCK/RX_19") (pintype "bidirectional"))
    )
    (net (code "8") (name "AP4_GP09{slash}TT_9DOF_H_MOSI") (class "Default")
      (node (ref "SJ5") (pin "3") (pinfunction "3_3") (pintype "passive"))
      (node (ref "U1") (pin "G2") (pinfunction "GPIO32_G2") (pintype "bidirectional"))
    )
    (net (code "9") (name "AP4_GP10{slash}TT_9DOF_H_MISO") (class "Default")
      (node (ref "SJ6") (pin "3") (pinfunction "3_3") (pintype "passive"))
      (node (ref "U1") (pin "G3") (pinfunction "GPIO33_G3") (pintype "bidirectional"))
    )
    (net (code "10") (name "AP4_GP13{slash}TT_9DOF_~{BOOT}") (class "Default")
      (node (ref "R14") (pin "1") (pinfunction "1_1") (pintype "passive"))
      (node (ref "U1") (pin "D5") (pinfunction "GPIO13_D5") (pintype "bidirectional"))
      (node (ref "U6") (pin "4") (pinfunction "~{BOOT}_4") (pintype "input"))
    )
    (net (code "11") (name "AP4_GP14{slash}TT_~{DW_SPI_CS}") (class "Default")
      (node (ref "TP12") (pin "P$1") (pinfunction "TESTPOINT_P$1") (pintype "bidirectional"))
      (node (ref "U1") (pin "D6") (pinfunction "GPIO14_D6") (pintype "bidirectional"))
      (node (ref "U2") (pin "B5") (pinfunction "~{SPICS}_B5") (pintype "bidirectional"))
    )
    (net (code "12") (name "AP4_GP17{slash}TT_9DOF_H_~{INT}") (class "Default")
      (node (ref "U1") (pin "D4") (pinfunction "GPIO17_D4") (pintype "bidirectional"))
      (node (ref "U6") (pin "14") (pinfunction "H_INTN_14") (pintype "output"))
    )
    (net (code "13") (name "AP4_GP18{slash}TT_BATIN") (class "Default")
      (node (ref "C31") (pin "1") (pinfunction "1_1") (pintype "bidirectional"))
      (node (ref "R27") (pin "2") (pinfunction "2_2") (pintype "passive"))
      (node (ref "R28") (pin "1") (pinfunction "1_1") (pintype "passive"))
      (node (ref "U1") (pin "D3") (pinfunction "GPIO18_D3") (pintype "bidirectional"))
    )
    (net (code "14") (name "AP4_GP24{slash}TT_RFSW_V1") (class "Default")
      (node (ref "S2") (pin "4") (pinfunction "V1_4") (pintype "input"))
      (node (ref "U1") (pin "E2") (pinfunction "GPIO24_E2") (pintype "bidirectional"))
    )
    (net (code "15") (name "AP4_GP25{slash}TT_RFSW_V2") (class "Default")
      (node (ref "S2") (pin "5") (pinfunction "V2_5") (pintype "input"))
      (node (ref "U1") (pin "K5") (pinfunction "GPIO25_K5") (pintype "bidirectional"))
    )
    (net (code "16") (name "AP4_GP26{slash}TT_DW_WAKEUP") (class "Default")
      (node (ref "U1") (pin "L5") (pinfunction "GPIO26_L5") (pintype "bidirectional"))
      (node (ref "U2") (pin "B9") (pinfunction "WAKEUP_B9") (pintype "bidirectional"))
    )
    (net (code "17") (name "AP4_GP27{slash}TT_DW_IRQ") (class "Default")
      (node (ref "R19") (pin "2") (pinfunction "2_2") (pintype "passive"))
      (node (ref "U1") (pin "M5") (pinfunction "GPIO27_M5") (pintype "bidirectional"))
      (node (ref "U2") (pin "B1") (pinfunction "IRQ/GPIO8_B1") (pintype "bidirectional"))
    )
    (net (code "18") (name "AP4_GP30{slash}TT_FLASH_~{WP}") (class "Default")
      (node (ref "U1") (pin "G4") (pinfunction "GPIO30_G4") (pintype "bidirectional"))
      (node (ref "U8") (pin "3") (pinfunction "~{WP}/SIO2_3") (pintype "bidirectional"))
    )
    (net (code "19") (name "AP4_GP31{slash}TT_DW_SPI_CLK") (class "Default")
      (node (ref "TP11") (pin "P$1") (pinfunction "TESTPOINT_P$1") (pintype "bidirectional"))
      (node (ref "U1") (pin "E8") (pinfunction "GPIO8_E8") (pintype "bidirectional"))
      (node (ref "U2") (pin "A8") (pinfunction "SPICLK_A8") (pintype "bidirectional"))
    )
    (net (code "20") (name "AP4_GP32{slash}TT_DW_SPI_IO0") (class "Default")
      (node (ref "TP13") (pin "P$1") (pinfunction "TESTPOINT_P$1") (pintype "bidirectional"))
      (node (ref "U1") (pin "E7") (pinfunction "GPIO9_E7") (pintype "bidirectional"))
      (node (ref "U2") (pin "B7") (pinfunction "SPICDI(MOSI)_B7") (pintype "bidirectional"))
    )
    (net (code "21") (name "AP4_GP33{slash}TT_DW_SPI_IO1") (class "Default")
      (node (ref "TP14") (pin "P$1") (pinfunction "TESTPOINT_P$1") (pintype "bidirectional"))
      (node (ref "U1") (pin "E6") (pinfunction "GPIO10_E6") (pintype "bidirectional"))
      (node (ref "U2") (pin "A6") (pinfunction "SPICDO(MISO)_A6") (pintype "bidirectional"))
    )
    (net (code "22") (name "AP4_GP47{slash}TT_FLASH_SCK") (class "Default")
      (node (ref "U1") (pin "F1") (pinfunction "GPIO47_F1") (pintype "bidirectional"))
      (node (ref "U8") (pin "6") (pinfunction "SCLK_6") (pintype "input"))
    )
    (net (code "23") (name "AP4_GP48{slash}TT_FLASH_PDI_IO0") (class "Default")
      (node (ref "U1") (pin "E1") (pinfunction "GPIO48_E1") (pintype "bidirectional"))
      (node (ref "U8") (pin "5") (pinfunction "SI/SIO0_5") (pintype "bidirectional"))
    )
    (net (code "24") (name "AP4_GP49{slash}TT_FLASH_PDO_IO1") (class "Default")
      (node (ref "U1") (pin "D1") (pinfunction "GPIO49_D1") (pintype "bidirectional"))
      (node (ref "U8") (pin "2") (pinfunction "SO/SIO1_2") (pintype "bidirectional"))
    )
    (net (code "25") (name "AP4_GP50{slash}TT_~{DW_RESET}") (class "Default")
      (node (ref "TP15") (pin "P$1") (pinfunction "TESTPOINT_P$1") (pintype "bidirectional"))
      (node (ref "U1") (pin "A9") (pinfunction "GPIO50_A9") (pintype "bidirectional"))
      (node (ref "U2") (pin "A10") (pinfunction "~{RST}_A10") (pintype "bidirectional"))
    )
    (net (code "26") (name "AP4_GP51{slash}LED1_GREEN") (class "Default")
      (node (ref "R2") (pin "2") (pinfunction "2_2") (pintype "passive"))
      (node (ref "U1") (pin "B9") (pinfunction "GPIO51_B9") (pintype "bidirectional"))
    )
    (net (code "27") (name "AP4_GP53{slash}LED1_RED") (class "Default")
      (node (ref "R5") (pin "2") (pinfunction "2_2") (pintype "passive"))
      (node (ref "U1") (pin "C9") (pinfunction "GPIO53_C9") (pintype "bidirectional"))
    )
    (net (code "28") (name "AP4_GP55{slash}TT_BUZZER_GATE") (class "Default")
      (node (ref "Q2") (pin "G") (pinfunction "G_G") (pintype "passive"))
      (node (ref "R20") (pin "1") (pinfunction "1_1") (pintype "passive"))
      (node (ref "U1") (pin "D9") (pinfunction "GPIO55_D9") (pintype "bidirectional"))
    )
    (net (code "29") (name "AP4_GP58{slash}TT_~{CHG}") (class "Default")
      (node (ref "U1") (pin "J7") (pinfunction "GPIO58_J7") (pintype "bidirectional"))
      (node (ref "U3") (pin "8") (pinfunction "~{CHG}_8") (pintype "bidirectional"))
      (node (ref "U4") (pin "7") (pinfunction "~{CHG}_7") (pintype "bidirectional"))
    )
    (net (code "30") (name "AP4_GP60{slash}TT_~{PG}") (class "Default")
      (node (ref "U1") (pin "K8") (pinfunction "GPIO60_K8") (pintype "bidirectional"))
      (node (ref "U3") (pin "5") (pinfunction "~{PG}_5") (pintype "bidirectional"))
    )
    (net (code "31") (name "AP4_GP63{slash}TT_9DOF_PS0{slash}WAKE") (class "Default")
      (node (ref "U1") (pin "M6") (pinfunction "GPIO63_M6") (pintype "bidirectional"))
      (node (ref "U6") (pin "6") (pinfunction "PS0/WAKE_6") (pintype "input"))
    )
    (net (code "32") (name "AP4_GP65{slash}TT_9DOF_~{RESET}") (class "Default")
      (node (ref "U1") (pin "A7") (pinfunction "GPIO65_A7") (pintype "bidirectional"))
      (node (ref "U6") (pin "11") (pinfunction "~{RESET}_11") (pintype "input"))
    )
    (net (code "33") (name "AP4_GP66{slash}TT_QI_TS_CTRL") (class "Default")
      (node (ref "C34") (pin "1") (pinfunction "1_1") (pintype "bidirectional"))
      (node (ref "RT1") (pin "2") (pinfunction "2_2") (pintype "passive"))
      (node (ref "U1") (pin "A8") (pinfunction "GPIO66_A8") (pintype "bidirectional"))
      (node (ref "U4") (pin "13") (pinfunction "TS/CTRL_13") (pintype "bidirectional"))
    )
    (net (code "34") (name "AP4_GP69{slash}TT_FLASH_~{CS}") (class "Default")
      (node (ref "RX3") (pin "1") (pinfunction "1_1") (pintype "passive"))
      (node (ref "U1") (pin "B8") (pinfunction "GPIO69_B8") (pintype "bidirectional"))
      (node (ref "U8") (pin "1") (pinfunction "~{CS}_1") (pintype "input"))
    )
    (net (code "35") (name "AP4_GP72{slash}TT_9DOF_H_~{CS}") (class "Default")
      (node (ref "U1") (pin "C8") (pinfunction "GPIO72_C8") (pintype "bidirectional"))
      (node (ref "U6") (pin "18") (pinfunction "H_~{CS}_18") (pintype "input"))
    )
    (net (code "36") (name "AP4_GP78{slash}VR-EN_USB0P9") (class "Default")
      (node (ref "U1") (pin "L11") (pinfunction "GPIO78_L11") (pintype "bidirectional"))
      (node (ref "VR5") (pin "3") (pinfunction "EN_3") (pintype "input"))
    )
    (net (code "37") (name "AP4_GP79{slash}LED2_RED") (class "Default")
      (node (ref "R4") (pin "2") (pinfunction "2_2") (pintype "passive"))
      (node (ref "U1") (pin "M11") (pinfunction "GPIO79_M11") (pintype "bidirectional"))
    )
    (net (code "38") (name "AP4_GP80{slash}USB_CABLE_DETECT") (class "Default")
      (node (ref "R23") (pin "2") (pinfunction "2_2") (pintype "passive"))
      (node (ref "R26") (pin "1") (pinfunction "1_1") (pintype "passive"))
      (node (ref "U1") (pin "K10") (pinfunction "GPIO80_K10") (pintype "bidirectional"))
    )
    (net (code "39") (name "AP4_GP81{slash}VR-EN_USB3P3") (class "Default")
      (node (ref "U1") (pin "L10") (pinfunction "GPIO81_L10") (pintype "bidirectional"))
      (node (ref "VR4") (pin "3") (pinfunction "EN_3") (pintype "input"))
    )
    (net (code "40") (name "AP4_GP88{slash}LED2_YLW") (class "Default")
      (node (ref "R3") (pin "2") (pinfunction "2_2") (pintype "passive"))
      (node (ref "U1") (pin "F9") (pinfunction "GPIO88_F9") (pintype "bidirectional"))
    )
    (net (code "41") (name "AP4_SWDCLK") (class "Default")
      (node (ref "J1") (pin "4") (pinfunction "SWDCLK_4") (pintype "bidirectional"))
      (node (ref "J1") (pin "B4") (pinfunction "SWDCLK_B4") (pintype "bidirectional"))
      (node (ref "U1") (pin "K3") (pinfunction "GPIO20_K3") (pintype "bidirectional"))
    )
    (net (code "42") (name "AP4_SWDIO") (class "Default")
      (node (ref "J1") (pin "2") (pinfunction "SWDIO_2") (pintype "bidirectional"))
      (node (ref "J1") (pin "B2") (pinfunction "SWDIO_B2") (pintype "bidirectional"))
      (node (ref "U1") (pin "J3") (pinfunction "GPIO21_J3") (pintype "bidirectional"))
    )
    (net (code "43") (name "AP4_SWO") (class "Default")
      (node (ref "J1") (pin "6") (pinfunction "SWO_6") (pintype "bidirectional"))
      (node (ref "J1") (pin "B6") (pinfunction "SWO_B6") (pintype "bidirectional"))
      (node (ref "U1") (pin "L4") (pinfunction "GPIO3_L4") (pintype "bidirectional"))
    )
    (net (code "44") (name "AP4_USB0_N") (class "Default")
      (node (ref "D5") (pin "3") (pinfunction "I/O2_3") (pintype "bidirectional"))
      (node (ref "J7") (pin "A7") (pinfunction "DN1_A7") (pintype "bidirectional"))
      (node (ref "J7") (pin "B7") (pinfunction "DN2_B7") (pintype "bidirectional"))
      (node (ref "U1") (pin "M8") (pinfunction "USB0PN_M8") (pintype "bidirectional"))
    )
    (net (code "45") (name "AP4_USB0_P") (class "Default")
      (node (ref "D5") (pin "2") (pinfunction "I/O1_2") (pintype "bidirectional"))
      (node (ref "J7") (pin "A6") (pinfunction "DP1_A6") (pintype "bidirectional"))
      (node (ref "J7") (pin "B6") (pinfunction "DP2_B6") (pintype "bidirectional"))
      (node (ref "U1") (pin "M7") (pinfunction "USB0PP_M7") (pintype "bidirectional"))
    )
    (net (code "46") (name "AP4_VDDBH") (class "Default")
      (node (ref "C75") (pin "1") (pinfunction "1_1") (pintype "bidirectional"))
      (node (ref "L6") (pin "2") (pinfunction "2_2") (pintype "bidirectional"))
      (node (ref "RZ1") (pin "1") (pinfunction "1_1") (pintype "passive"))
      (node (ref "TP8") (pin "P$1") (pinfunction "TESTPOINT_P$1") (pintype "bidirectional"))
      (node (ref "U1") (pin "G12") (pinfunction "VDDBH--BLE_BUCK_VOUT_G12") (pintype "bidirectional"))
    )
    (net (code "47") (name "AP4_VDDBH_RF") (class "Default")
      (node (ref "C46") (pin "P$1") (pinfunction "1_P$1") (pintype "bidirectional"))
      (node (ref "RZ1") (pin "2") (pinfunction "2_2") (pintype "passive"))
      (node (ref "U1") (pin "J1") (pinfunction "VDDBH_RF--BLE_BUCK_RF_VOUT_J1") (pintype "bidirectional"))
    )
    (net (code "48") (name "AP4_VDDB_SUP") (class "Default")
      (node (ref "C72") (pin "P$1") (pinfunction "1_P$1") (pintype "bidirectional"))
      (node (ref "C73") (pin "P$1") (pinfunction "1_P$1") (pintype "bidirectional"))
      (node (ref "SJ8") (pin "2") (pinfunction "2_2") (pintype "passive"))
      (node (ref "U1") (pin "G1") (pinfunction "VDDB-BLE_SUPPLY_G1") (pintype "bidirectional"))
    )
    (net (code "49") (name "AP4_VDDF") (class "Default")
      (node (ref "C65") (pin "P$1") (pinfunction "1_P$1") (pintype "bidirectional"))
      (node (ref "C71") (pin "P$1") (pinfunction "1_P$1") (pintype "bidirectional"))
      (node (ref "TP10") (pin "P$1") (pinfunction "TESTPOINT_P$1") (pintype "bidirectional"))
      (node (ref "U1") (pin "C2") (pinfunction "VDDF-MEM_C2") (pintype "bidirectional"))
    )
    (net (code "50") (name "AP4_VDDMIPI_1P8") (class "Default")
      (node (ref "C66") (pin "P$1") (pinfunction "1_P$1") (pintype "bidirectional"))
      (node (ref "SJ7") (pin "1") (pinfunction "1_1") (pintype "passive"))
      (node (ref "U1") (pin "H10") (pinfunction "VDD18-MIPI_H10") (pintype "bidirectional"))
    )
    (net (code "51") (name "AP4_VDDUSB_0P9") (class "Default")
      (node (ref "C69") (pin "P$1") (pinfunction "1_P$1") (pintype "bidirectional"))
      (node (ref "SJ9") (pin "1") (pinfunction "1_1") (pintype "passive"))
      (node (ref "U1") (pin "L7") (pinfunction "VDDUSB0P9_L7") (pintype "bidirectional"))
    )
    (net (code "52") (name "AP4_VDDUSB_3P3") (class "Default")
      (node (ref "C70") (pin "P$1") (pinfunction "1_P$1") (pintype "bidirectional"))
      (node (ref "SJ10") (pin "1") (pinfunction "1_1") (pintype "passive"))
      (node (ref "U1") (pin "K7") (pinfunction "VDDUSB33_K7") (pintype "bidirectional"))
    )
    (net (code "53") (name "AP4_~{RESET}") (class "Default")
      (node (ref "C17") (pin "P$2") (pinfunction "P$2_P$2") (pintype "bidirectional"))
      (node (ref "D3") (pin "1") (pinfunction "C_1") (pintype "passive"))
      (node (ref "J1") (pin "3") (pinfunction "~{RESET}_3") (pintype "bidirectional"))
      (node (ref "J1") (pin "B3") (pinfunction "~{RESET}_B3") (pintype "bidirectional"))
      (node (ref "U1") (pin "A6") (pinfunction "~{RST}_A6") (pintype "input"))
    )
    (net (code "54") (name "BATT_THERM") (class "Default")
      (node (ref "J4") (pin "2") (pinfunction "2_2") (pintype "bidirectional"))
      (node (ref "J4") (pin "2SUPP") (pinfunction "2_2SUPP") (pintype "bidirectional"))
      (node (ref "SJ1") (pin "3") (pinfunction "3_3") (pintype "passive"))
    )
    (net (code "55") (name "BATT_TS") (class "Default")
      (node (ref "SJ1") (pin "2") (pinfunction "2_2") (pintype "passive"))
      (node (ref "U3") (pin "9") (pinfunction "TS_9") (pintype "bidirectional"))
    )
    (net (code "56") (name "BNO_ENV_SCL") (class "Default")
      (node (ref "R15") (pin "1") (pinfunction "1_1") (pintype "passive"))
      (node (ref "U6") (pin "15") (pinfunction "ENV_SCL_15") (pintype "bidirectional"))
    )
    (net (code "57") (name "BNO_ENV_SDA") (class "Default")
      (node (ref "R16") (pin "1") (pinfunction "1_1") (pintype "passive"))
      (node (ref "U6") (pin "16") (pinfunction "ENV_SDA_16") (pintype "bidirectional"))
    )
    (net (code "58") (name "DW_EXTON") (class "Default")
      (node (ref "S3") (pin "2") (pinfunction "CTL_2") (pintype "bidirectional"))
      (node (ref "S3") (pin "3") (pinfunction "CTL_3") (pintype "bidirectional"))
      (node (ref "SJ2") (pin "2") (pinfunction "2_2") (pintype "passive"))
      (node (ref "VR3") (pin "3") (pinfunction "EN_3") (pintype "input"))
    )
    (net (code "59") (name "DW_EXTON_RAW") (class "Default")
      (node (ref "SJ2") (pin "3") (pinfunction "3_3") (pintype "passive"))
      (node (ref "U2") (pin "A12") (pinfunction "EXTON_A12") (pintype "bidirectional"))
    )
    (net (code "60") (name "DW_GPIO6{slash}EXTRXE") (class "Default")
      (node (ref "SJ3") (pin "3") (pinfunction "3_3") (pintype "passive"))
      (node (ref "TP6") (pin "P$1") (pinfunction "TESTPOINT_P$1") (pintype "bidirectional"))
      (node (ref "U2") (pin "C4") (pinfunction "GPIO6/EXTRXE/SPIPHA_C4") (pintype "bidirectional"))
    )
    (net (code "61") (name "DW_RF1_BLKD") (class "Default")
      (node (ref "C2") (pin "P$2") (pinfunction "2_P$2") (pintype "bidirectional"))
      (node (ref "U7") (pin "6") (pinfunction "LNA_OUT_6") (pintype "bidirectional"))
    )
    (net (code "62") (name "DW_SYNC") (class "Default")
      (node (ref "TP7") (pin "P$1") (pinfunction "TESTPOINT_P$1") (pintype "bidirectional"))
      (node (ref "U2") (pin "G2") (pinfunction "GPIO7/SYNC_G2") (pintype "bidirectional"))
    )
    (net (code "63") (name "DW_VDD2_SUP") (class "Default")
      (node (ref "C15") (pin "P$1") (pinfunction "P$1_P$1") (pintype "bidirectional"))
      (node (ref "C28") (pin "P$1") (pinfunction "P$1_P$1") (pintype "bidirectional"))
      (node (ref "C86") (pin "P$1") (pinfunction "P$1_P$1") (pintype "bidirectional"))
      (node (ref "FB1") (pin "P$1") (pinfunction "P$1_P$1") (pintype "bidirectional"))
      (node (ref "RZ2") (pin "2") (pinfunction "2_2") (pintype "passive"))
      (node (ref "U2") (pin "B15") (pinfunction "VDD2B_B15") (pintype "bidirectional"))
    )
    (net (code "64") (name "DW_VDD3_SUP") (class "Default")
      (node (ref "C16") (pin "P$2") (pinfunction "P$2_P$2") (pintype "bidirectional"))
      (node (ref "C26") (pin "P$2") (pinfunction "P$2_P$2") (pintype "bidirectional"))
      (node (ref "C85") (pin "P$2") (pinfunction "P$2_P$2") (pintype "bidirectional"))
      (node (ref "RZ3") (pin "2") (pinfunction "2_2") (pintype "passive"))
      (node (ref "U2") (pin "D15") (pinfunction "VDD3_D15") (pintype "bidirectional"))
    )
    (net (code "65") (name "GND") (class "Default")
      (node (ref "C11") (pin "P$2") (pinfunction "P$2_P$2") (pintype "bidirectional"))
      (node (ref "C14") (pin "P$2") (pinfunction "P$2_P$2") (pintype "bidirectional"))
      (node (ref "C15") (pin "P$2") (pinfunction "P$2_P$2") (pintype "bidirectional"))
      (node (ref "C16") (pin "P$1") (pinfunction "P$1_P$1") (pintype "bidirectional"))
      (node (ref "C17") (pin "P$1") (pinfunction "P$1_P$1") (pintype "bidirectional"))
      (node (ref "C25") (pin "P$2") (pinfunction "P$2_P$2") (pintype "bidirectional"))
      (node (ref "C26") (pin "P$1") (pinfunction "P$1_P$1") (pintype "bidirectional"))
      (node (ref "C27") (pin "2") (pinfunction "2_2") (pintype "bidirectional"))
      (node (ref "C28") (pin "P$2") (pinfunction "P$2_P$2") (pintype "bidirectional"))
      (node (ref "C29") (pin "2") (pinfunction "2_2") (pintype "bidirectional"))
      (node (ref "C3") (pin "P$2") (pinfunction "P$2_P$2") (pintype "bidirectional"))
      (node (ref "C30") (pin "2") (pinfunction "2_2") (pintype "bidirectional"))
      (node (ref "C31") (pin "2") (pinfunction "2_2") (pintype "bidirectional"))
      (node (ref "C32") (pin "2") (pinfunction "2_2") (pintype "bidirectional"))
      (node (ref "C33") (pin "2") (pinfunction "2_2") (pintype "bidirectional"))
      (node (ref "C34") (pin "2") (pinfunction "2_2") (pintype "bidirectional"))
      (node (ref "C35") (pin "2") (pinfunction "2_2") (pintype "bidirectional"))
      (node (ref "C36") (pin "2") (pinfunction "2_2") (pintype "bidirectional"))
      (node (ref "C37") (pin "2") (pinfunction "2_2") (pintype "bidirectional"))
      (node (ref "C38") (pin "2") (pinfunction "2_2") (pintype "bidirectional"))
      (node (ref "C39") (pin "2") (pinfunction "2_2") (pintype "bidirectional"))
      (node (ref "C4") (pin "P$2") (pinfunction "P$2_P$2") (pintype "bidirectional"))
      (node (ref "C40") (pin "2") (pinfunction "2_2") (pintype "bidirectional"))
      (node (ref "C41") (pin "P$1") (pinfunction "P$1_P$1") (pintype "bidirectional"))
      (node (ref "C44") (pin "P$2") (pinfunction "2_P$2") (pintype "bidirectional"))
      (node (ref "C45") (pin "P$2") (pinfunction "2_P$2") (pintype "bidirectional"))
      (node (ref "C47") (pin "P$2") (pinfunction "2_P$2") (pintype "bidirectional"))
      (node (ref "C48") (pin "P$2") (pinfunction "2_P$2") (pintype "bidirectional"))
      (node (ref "C49") (pin "P$1") (pinfunction "1_P$1") (pintype "bidirectional"))
      (node (ref "C5") (pin "P$1") (pinfunction "1_P$1") (pintype "bidirectional"))
      (node (ref "C50") (pin "P$2") (pinfunction "2_P$2") (pintype "bidirectional"))
      (node (ref "C51") (pin "P$2") (pinfunction "2_P$2") (pintype "bidirectional"))
      (node (ref "C52") (pin "P$2") (pinfunction "2_P$2") (pintype "bidirectional"))
      (node (ref "C53") (pin "P$2") (pinfunction "2_P$2") (pintype "bidirectional"))
      (node (ref "C54") (pin "P$2") (pinfunction "2_P$2") (pintype "bidirectional"))
      (node (ref "C55") (pin "P$2") (pinfunction "2_P$2") (pintype "bidirectional"))
      (node (ref "C56") (pin "P$2") (pinfunction "2_P$2") (pintype "bidirectional"))
      (node (ref "C57") (pin "P$2") (pinfunction "2_P$2") (pintype "bidirectional"))
      (node (ref "C58") (pin "P$2") (pinfunction "2_P$2") (pintype "bidirectional"))
      (node (ref "C59") (pin "P$2") (pinfunction "2_P$2") (pintype "bidirectional"))
      (node (ref "C6") (pin "P$1") (pinfunction "1_P$1") (pintype "bidirectional"))
      (node (ref "C60") (pin "P$1") (pinfunction "1_P$1") (pintype "bidirectional"))
      (node (ref "C61") (pin "P$1") (pinfunction "1_P$1") (pintype "bidirectional"))
      (node (ref "C62") (pin "P$2") (pinfunction "2_P$2") (pintype "bidirectional"))
      (node (ref "C63") (pin "P$2") (pinfunction "2_P$2") (pintype "bidirectional"))
      (node (ref "C64") (pin "P$2") (pinfunction "2_P$2") (pintype "bidirectional"))
      (node (ref "C65") (pin "P$2") (pinfunction "2_P$2") (pintype "bidirectional"))
      (node (ref "C66") (pin "P$2") (pinfunction "2_P$2") (pintype "bidirectional"))
      (node (ref "C67") (pin "P$1") (pinfunction "1_P$1") (pintype "bidirectional"))
      (node (ref "C68") (pin "P$2") (pinfunction "2_P$2") (pintype "bidirectional"))
      (node (ref "C69") (pin "P$2") (pinfunction "2_P$2") (pintype "bidirectional"))
      (node (ref "C7") (pin "2") (pinfunction "2_2") (pintype "passive"))
      (node (ref "C70") (pin "P$2") (pinfunction "2_P$2") (pintype "bidirectional"))
      (node (ref "C72") (pin "P$2") (pinfunction "2_P$2") (pintype "bidirectional"))
      (node (ref "C73") (pin "P$2") (pinfunction "2_P$2") (pintype "bidirectional"))
      (node (ref "C74") (pin "P$2") (pinfunction "2_P$2") (pintype "bidirectional"))
      (node (ref "C75") (pin "2") (pinfunction "2_2") (pintype "bidirectional"))
      (node (ref "C76") (pin "1") (pinfunction "1_1") (pintype "bidirectional"))
      (node (ref "C77") (pin "2") (pinfunction "2_2") (pintype "bidirectional"))
      (node (ref "C78") (pin "1") (pinfunction "1_1") (pintype "bidirectional"))
      (node (ref "C79") (pin "2") (pinfunction "2_2") (pintype "bidirectional"))
      (node (ref "C8") (pin "2") (pinfunction "2_2") (pintype "passive"))
      (node (ref "C80") (pin "2") (pinfunction "2_2") (pintype "bidirectional"))
      (node (ref "C81") (pin "1") (pinfunction "1_1") (pintype "bidirectional"))
      (node (ref "C82") (pin "2") (pinfunction "2_2") (pintype "bidirectional"))
      (node (ref "C83") (pin "2") (pinfunction "2_2") (pintype "bidirectional"))
      (node (ref "C84") (pin "2") (pinfunction "2_2") (pintype "bidirectional"))
      (node (ref "C85") (pin "P$1") (pinfunction "P$1_P$1") (pintype "bidirectional"))
      (node (ref "C86") (pin "P$2") (pinfunction "P$2_P$2") (pintype "bidirectional"))
      (node (ref "CX1") (pin "2") (pinfunction "2_2") (pintype "passive"))
      (node (ref "CX2") (pin "2") (pinfunction "2_2") (pintype "passive"))
      (node (ref "D3") (pin "2") (pinfunction "A_2") (pintype "passive"))
      (node (ref "D5") (pin "1") (pinfunction "GND_1") (pintype "bidirectional"))
      (node (ref "J1") (pin "5") (pinfunction "GND_5") (pintype "bidirectional"))
      (node (ref "J1") (pin "B5") (pinfunction "GND_B5") (pintype "bidirectional"))
      (node (ref "J3") (pin "2") (pinfunction "2_2") (pintype "passive"))
      (node (ref "J4") (pin "1") (pinfunction "1_1") (pintype "bidirectional"))
      (node (ref "J4") (pin "1SUPP") (pinfunction "1_1SUPP") (pintype "bidirectional"))
      (node (ref "J7") (pin "A1/B12") (pinfunction "GND_A1/B12") (pintype "power_in"))
      (node (ref "J7") (pin "B1/A12") (pinfunction "GND_B1/A12") (pintype "power_in"))
      (node (ref "J7") (pin "S1") (pinfunction "GND_S1") (pintype "power_in"))
      (node (ref "J7") (pin "S2") (pinfunction "GND_S2") (pintype "power_in"))
      (node (ref "J7") (pin "S3") (pinfunction "GND_S3") (pintype "power_in"))
      (node (ref "J7") (pin "S4") (pinfunction "GND_S4") (pintype "power_in"))
      (node (ref "Q2") (pin "S") (pinfunction "S_S") (pintype "passive"))
      (node (ref "R1") (pin "2") (pinfunction "2_2") (pintype "passive"))
      (node (ref "R10") (pin "1") (pinfunction "1_1") (pintype "passive"))
      (node (ref "R11") (pin "1") (pinfunction "1_1") (pintype "passive"))
      (node (ref "R12") (pin "2") (pinfunction "2_2") (pintype "passive"))
      (node (ref "R13") (pin "2") (pinfunction "2_2") (pintype "passive"))
      (node (ref "R19") (pin "1") (pinfunction "1_1") (pintype "passive"))
      (node (ref "R20") (pin "2") (pinfunction "2_2") (pintype "passive"))
      (node (ref "R21") (pin "1") (pinfunction "1_1") (pintype "passive"))
      (node (ref "R22") (pin "1") (pinfunction "1_1") (pintype "passive"))
      (node (ref "R23") (pin "1") (pinfunction "1_1") (pintype "passive"))
      (node (ref "R27") (pin "1") (pinfunction "1_1") (pintype "passive"))
      (node (ref "R6") (pin "2") (pinfunction "2_2") (pintype "passive"))
      (node (ref "RX1") (pin "1") (pinfunction "1_1") (pintype "passive"))
      (node (ref "RX2") (pin "1") (pinfunction "1_1") (pintype "passive"))
      (node (ref "S2") (pin "10") (pinfunction "GND_10") (pintype "bidirectional"))
      (node (ref "S2") (pin "12") (pinfunction "GND_12") (pintype "bidirectional"))
      (node (ref "S2") (pin "2") (pinfunction "GND_2") (pintype "bidirectional"))
      (node (ref "S2") (pin "7") (pinfunction "GND_7") (pintype "bidirectional"))
      (node (ref "S2") (pin "8") (pinfunction "GND_8") (pintype "bidirectional"))
      (node (ref "S2") (pin "PAD") (pinfunction "GND_PAD") (pintype "bidirectional"))
      (node (ref "S3") (pin "6") (pinfunction "GND_6") (pintype "bidirectional"))
      (node (ref "S3") (pin "7") (pinfunction "GND_7") (pintype "bidirectional"))
      (node (ref "S3") (pin "PAD") (pinfunction "GND_PAD") (pintype "bidirectional"))
      (node (ref "SJ3") (pin "1") (pinfunction "1_1") (pintype "passive"))
      (node (ref "SJ4") (pin "1") (pinfunction "1_1") (pintype "passive"))
      (node (ref "SJ7") (pin "2") (pinfunction "2_2") (pintype "passive"))
      (node (ref "U1") (pin "B12") (pinfunction "VSSAUDA_B12") (pintype "bidirectional"))
      (node (ref "U1") (pin "B2") (pinfunction "VSSP-BUCK_REGS_GND_B2") (pintype "bidirectional"))
      (node (ref "U1") (pin "B5") (pinfunction "VSSA-ANALOG_GND_B5") (pintype "bidirectional"))
      (node (ref "U1") (pin "D2") (pinfunction "VSS-DGND_FOR_VDDF_AND_PADS_D2") (pintype "bidirectional"))
      (node (ref "U1") (pin "E12") (pinfunction "VSSAUDD_E12") (pintype "bidirectional"))
      (node (ref "U1") (pin "H1") (pinfunction "VSSB-BLE_UNREG_GND_H1") (pintype "bidirectional"))
      (node (ref "U1") (pin "J10") (pinfunction "VSS18-MIPI_J10") (pintype "bidirectional"))
      (node (ref "U1") (pin "L1") (pinfunction "VSSVCO-BLECORE_GND_FOR_VCO_L1") (pintype "bidirectional"))
      (node (ref "U1") (pin "L2") (pinfunction "VSSS-HVSIMOBUCK_GND_L2") (pintype "bidirectional"))
      (node (ref "U1") (pin "L8") (pinfunction "VSSAUSB_L8") (pintype "bidirectional"))
      (node (ref "U2") (pin "A14") (pinfunction "VSS1_A14") (pintype "bidirectional"))
      (node (ref "U2") (pin "A2") (pinfunction "VSS_A2") (pintype "bidirectional"))
      (node (ref "U2") (pin "B11") (pinfunction "VSS1_B11") (pintype "bidirectional"))
      (node (ref "U2") (pin "B3") (pinfunction "VSS_B3") (pintype "bidirectional"))
      (node (ref "U2") (pin "C10") (pinfunction "VSS1_C10") (pintype "bidirectional"))
      (node (ref "U2") (pin "C12") (pinfunction "VSS3_C12") (pintype "bidirectional"))
      (node (ref "U2") (pin "C6") (pinfunction "VSS_C6") (pintype "bidirectional"))
      (node (ref "U2") (pin "C8") (pinfunction "VSS1_C8") (pintype "bidirectional"))
      (node (ref "U2") (pin "D11") (pinfunction "VSS2_D11") (pintype "bidirectional"))
      (node (ref "U2") (pin "D13") (pinfunction "VSS3_D13") (pintype "bidirectional"))
      (node (ref "U2") (pin "D5") (pinfunction "VSS_D5") (pintype "bidirectional"))
      (node (ref "U2") (pin "D7") (pinfunction "VSS_D7") (pintype "bidirectional"))
      (node (ref "U2") (pin "D9") (pinfunction "VSS1_D9") (pintype "bidirectional"))
      (node (ref "U2") (pin "E10") (pinfunction "GND-RF_E10") (pintype "bidirectional"))
      (node (ref "U2") (pin "E12") (pinfunction "GND-RF_E12") (pintype "bidirectional"))
      (node (ref "U2") (pin "E14") (pinfunction "VSS2_E14") (pintype "bidirectional"))
      (node (ref "U2") (pin "E6") (pinfunction "GND-RF_E6") (pintype "bidirectional"))
      (node (ref "U2") (pin "F7") (pinfunction "GND-RF_F7") (pintype "bidirectional"))
      (node (ref "U2") (pin "F9") (pinfunction "GND-RF_F9") (pintype "bidirectional"))
      (node (ref "U2") (pin "G10") (pinfunction "GND-RF_G10") (pintype "bidirectional"))
      (node (ref "U2") (pin "G6") (pinfunction "GND-RF_G6") (pintype "bidirectional"))
      (node (ref "U2") (pin "H1") (pinfunction "GND-RF_H1") (pintype "bidirectional"))
      (node (ref "U2") (pin "H13") (pinfunction "GND-RF_H13") (pintype "bidirectional"))
      (node (ref "U2") (pin "H3") (pinfunction "GND-RF_H3") (pintype "bidirectional"))
      (node (ref "U2") (pin "H7") (pinfunction "GND-RF_H7") (pintype "bidirectional"))
      (node (ref "U2") (pin "H9") (pinfunction "GND-RF_H9") (pintype "bidirectional"))
      (node (ref "U3") (pin "3") (pinfunction "VSS_3") (pintype "bidirectional"))
      (node (ref "U3") (pin "7") (pinfunction "ISET2_7") (pintype "bidirectional"))
      (node (ref "U3") (pin "PAD") (pinfunction "VSS_PAD") (pintype "bidirectional"))
      (node (ref "U4") (pin "1") (pinfunction "PGND_1") (pintype "bidirectional"))
      (node (ref "U4") (pin "10") (pinfunction "EN1_10") (pintype "bidirectional"))
      (node (ref "U4") (pin "11") (pinfunction "EN2_11") (pintype "bidirectional"))
      (node (ref "U4") (pin "20") (pinfunction "PGND_20") (pintype "bidirectional"))
      (node (ref "U4") (pin "PAD") (pinfunction "PGND_PAD") (pintype "bidirectional"))
      (node (ref "U6") (pin "10") (pinfunction "CLKSEL0_10") (pintype "output"))
      (node (ref "U6") (pin "2") (pinfunction "GND_2") (pintype "bidirectional"))
      (node (ref "U6") (pin "25") (pinfunction "GNDIO_25") (pintype "bidirectional"))
      (node (ref "U7") (pin "3") (pinfunction "GND_3") (pintype "bidirectional"))
      (node (ref "U7") (pin "4") (pinfunction "GND_4") (pintype "bidirectional"))
      (node (ref "U7") (pin "5") (pinfunction "GND_5") (pintype "bidirectional"))
      (node (ref "U7") (pin "7") (pinfunction "GND_7") (pintype "bidirectional"))
      (node (ref "U7") (pin "9") (pinfunction "GND_9") (pintype "bidirectional"))
      (node (ref "U8") (pin "4") (pinfunction "GND_4") (pintype "bidirectional"))
      (node (ref "VR1") (pin "13") (pinfunction "GND2_13") (pintype "bidirectional"))
      (node (ref "VR1") (pin "3") (pinfunction "GND2_3") (pintype "bidirectional"))
      (node (ref "VR1") (pin "9") (pinfunction "GND1_9") (pintype "bidirectional"))
      (node (ref "VR2") (pin "2") (pinfunction "GND_2") (pintype "bidirectional"))
      (node (ref "VR2") (pin "PAD") (pinfunction "GND_PAD") (pintype "bidirectional"))
      (node (ref "VR3") (pin "2") (pinfunction "GND_2") (pintype "bidirectional"))
      (node (ref "VR3") (pin "PAD") (pinfunction "GND_PAD") (pintype "bidirectional"))
      (node (ref "VR4") (pin "2") (pinfunction "GND_2") (pintype "bidirectional"))
      (node (ref "VR4") (pin "PAD") (pinfunction "GND_PAD") (pintype "bidirectional"))
      (node (ref "VR5") (pin "2") (pinfunction "GND_2") (pintype "bidirectional"))
      (node (ref "X1") (pin "2") (pinfunction "GND_2") (pintype "bidirectional"))
      (node (ref "X1") (pin "4") (pinfunction "GND_4") (pintype "bidirectional"))
      (node (ref "X4") (pin "2") (pinfunction "GND_2") (pintype "bidirectional"))
      (node (ref "X4") (pin "4") (pinfunction "GND_4") (pintype "bidirectional"))
    )
    (net (code "66") (name "Net-(A4-ANTENNA)") (class "Default")
      (node (ref "A4") (pin "S1") (pinfunction "ANTENNA_S1") (pintype "bidirectional"))
      (node (ref "L8") (pin "2") (pinfunction "2_2") (pintype "passive"))
    )
    (net (code "67") (name "Net-(C1-Pad1)") (class "Default")
      (node (ref "C1") (pin "1") (pinfunction "1_1") (pintype "passive"))
      (node (ref "L7") (pin "2") (pinfunction "2_2") (pintype "passive"))
      (node (ref "L8") (pin "1") (pinfunction "1_1") (pintype "passive"))
    )
    (net (code "68") (name "Net-(C2-1)") (class "Default")
      (node (ref "C2") (pin "P$1") (pinfunction "1_P$1") (pintype "bidirectional"))
      (node (ref "U2") (pin "H11") (pinfunction "RF1_H11") (pintype "bidirectional"))
    )
    (net (code "69") (name "Net-(C5-2)") (class "Default")
      (node (ref "C5") (pin "P$2") (pinfunction "2_P$2") (pintype "bidirectional"))
      (node (ref "U6") (pin "27") (pinfunction "XIN32_27") (pintype "bidirectional"))
      (node (ref "X2") (pin "2") (pinfunction "2_2") (pintype "bidirectional"))
    )
    (net (code "70") (name "Net-(C6-2)") (class "Default")
      (node (ref "C6") (pin "P$2") (pinfunction "2_P$2") (pintype "bidirectional"))
      (node (ref "U6") (pin "26") (pinfunction "XOUT32/CLKSEL1_26") (pintype "bidirectional"))
      (node (ref "X2") (pin "1") (pinfunction "1_1") (pintype "bidirectional"))
    )
    (net (code "71") (name "Net-(C9-2)") (class "Default")
      (node (ref "C9") (pin "P$2") (pinfunction "2_P$2") (pintype "bidirectional"))
      (node (ref "R21") (pin "2") (pinfunction "2_2") (pintype "passive"))
      (node (ref "R24") (pin "1") (pinfunction "1_1") (pintype "passive"))
      (node (ref "VR1") (pin "10") (pinfunction "FB2_10") (pintype "bidirectional"))
    )
    (net (code "72") (name "Net-(C10-1)") (class "Default")
      (node (ref "C10") (pin "P$1") (pinfunction "1_P$1") (pintype "bidirectional"))
      (node (ref "R22") (pin "2") (pinfunction "2_2") (pintype "passive"))
      (node (ref "R25") (pin "2") (pinfunction "2_2") (pintype "passive"))
      (node (ref "VR1") (pin "4") (pinfunction "FB1_4") (pintype "bidirectional"))
    )
    (net (code "73") (name "Net-(C45-1)") (class "Default")
      (node (ref "C11") (pin "P$1") (pinfunction "P$1_P$1") (pintype "bidirectional"))
      (node (ref "C25") (pin "P$1") (pinfunction "P$1_P$1") (pintype "bidirectional"))
      (node (ref "C45") (pin "P$1") (pinfunction "1_P$1") (pintype "bidirectional"))
      (node (ref "U7") (pin "1") (pinfunction "VDD_1") (pintype "bidirectional"))
      (node (ref "VR3") (pin "1") (pinfunction "OUT_1") (pintype "power_in"))
    )
    (net (code "74") (name "Net-(C49-2)") (class "Default")
      (node (ref "C49") (pin "P$2") (pinfunction "2_P$2") (pintype "bidirectional"))
      (node (ref "U1") (pin "A12") (pinfunction "LPADC_VREF_A12") (pintype "bidirectional"))
    )
    (net (code "75") (name "Net-(C50-1)") (class "Default")
      (node (ref "C50") (pin "P$1") (pinfunction "1_P$1") (pintype "bidirectional"))
      (node (ref "SJ10") (pin "2") (pinfunction "2_2") (pintype "passive"))
      (node (ref "VR4") (pin "1") (pinfunction "OUT_1") (pintype "power_in"))
    )
    (net (code "76") (name "Net-(C52-1)") (class "Default")
      (node (ref "C52") (pin "P$1") (pinfunction "1_P$1") (pintype "bidirectional"))
      (node (ref "SJ9") (pin "2") (pinfunction "2_2") (pintype "passive"))
      (node (ref "VR5") (pin "5") (pinfunction "OUT_5") (pintype "power_in"))
    )
    (net (code "77") (name "Net-(C62-1)") (class "Default")
      (node (ref "C62") (pin "P$1") (pinfunction "1_P$1") (pintype "bidirectional"))
      (node (ref "U1") (pin "C1") (pinfunction "VDDS-SRAM_HV_SUP_C1") (pintype "bidirectional"))
    )
    (net (code "78") (name "Net-(C63-1)") (class "Default")
      (node (ref "C63") (pin "P$1") (pinfunction "1_P$1") (pintype "bidirectional"))
      (node (ref "U1") (pin "A3") (pinfunction "VDDC-CORE_A3") (pintype "bidirectional"))
    )
    (net (code "79") (name "Net-(C64-1)") (class "Default")
      (node (ref "C64") (pin "P$1") (pinfunction "1_P$1") (pintype "bidirectional"))
      (node (ref "U1") (pin "B3") (pinfunction "VDDC_LV-CORE_LV_B3") (pintype "bidirectional"))
    )
    (net (code "80") (name "Net-(C67-2)") (class "Default")
      (node (ref "C67") (pin "P$2") (pinfunction "2_P$2") (pintype "bidirectional"))
      (node (ref "U1") (pin "B10") (pinfunction "LPMICBIAS_B10") (pintype "output"))
    )
    (net (code "81") (name "Net-(D1-PadC1)") (class "Default")
      (node (ref "D1") (pin "C1") (pinfunction "C1_C1") (pintype "bidirectional"))
      (node (ref "R5") (pin "1") (pinfunction "1_1") (pintype "passive"))
    )
    (net (code "82") (name "Net-(D1-PadC2)") (class "Default")
      (node (ref "D1") (pin "C2") (pinfunction "C2_C2") (pintype "bidirectional"))
      (node (ref "R2") (pin "1") (pinfunction "1_1") (pintype "passive"))
    )
    (net (code "83") (name "Net-(D2-PadC1)") (class "Default")
      (node (ref "D2") (pin "C1") (pinfunction "C1_C1") (pintype "bidirectional"))
      (node (ref "R4") (pin "1") (pinfunction "1_1") (pintype "passive"))
    )
    (net (code "84") (name "Net-(D2-PadC2)") (class "Default")
      (node (ref "D2") (pin "C2") (pinfunction "C2_C2") (pintype "bidirectional"))
      (node (ref "R3") (pin "1") (pinfunction "1_1") (pintype "passive"))
    )
    (net (code "85") (name "Net-(J7-CC1)") (class "Default")
      (node (ref "J7") (pin "A5") (pinfunction "CC1_A5") (pintype "bidirectional"))
      (node (ref "R12") (pin "1") (pinfunction "1_1") (pintype "passive"))
    )
    (net (code "86") (name "Net-(J7-CC2)") (class "Default")
      (node (ref "J7") (pin "B5") (pinfunction "CC2_B5") (pintype "bidirectional"))
      (node (ref "R13") (pin "1") (pinfunction "1_1") (pintype "passive"))
    )
    (net (code "87") (name "Net-(L1-1)") (class "Default")
      (node (ref "L1") (pin "P$1") (pinfunction "1_P$1") (pintype "bidirectional"))
      (node (ref "VR1") (pin "2") (pinfunction "LX2_2") (pintype "bidirectional"))
    )
    (net (code "88") (name "Net-(L2-2)") (class "Default")
      (node (ref "L2") (pin "P$2") (pinfunction "2_P$2") (pintype "bidirectional"))
      (node (ref "VR1") (pin "8") (pinfunction "LX1_8") (pintype "bidirectional"))
    )
    (net (code "89") (name "Net-(L4-1)") (class "Default")
      (node (ref "C20") (pin "2") (pinfunction "2_2") (pintype "bidirectional"))
      (node (ref "C21") (pin "2") (pinfunction "2_2") (pintype "bidirectional"))
      (node (ref "C22") (pin "2") (pinfunction "2_2") (pintype "bidirectional"))
      (node (ref "L4") (pin "P$1") (pinfunction "1_P$1") (pintype "bidirectional"))
    )
    (net (code "90") (name "Net-(L4-2)") (class "Default")
      (node (ref "C12") (pin "2") (pinfunction "2_2") (pintype "bidirectional"))
      (node (ref "C13") (pin "2") (pinfunction "2_2") (pintype "bidirectional"))
      (node (ref "C19") (pin "2") (pinfunction "2_2") (pintype "bidirectional"))
      (node (ref "C24") (pin "2") (pinfunction "2_2") (pintype "bidirectional"))
      (node (ref "C43") (pin "2") (pinfunction "2_2") (pintype "bidirectional"))
      (node (ref "L4") (pin "P$2") (pinfunction "2_P$2") (pintype "bidirectional"))
      (node (ref "U4") (pin "19") (pinfunction "AC2_19") (pintype "bidirectional"))
    )
    (net (code "91") (name "Net-(L5-1)") (class "Default")
      (node (ref "L5") (pin "P$1") (pinfunction "1_P$1") (pintype "bidirectional"))
      (node (ref "U1") (pin "A1") (pinfunction "SIMOBUCK_SW_A1") (pintype "bidirectional"))
    )
    (net (code "92") (name "Net-(L5-2)") (class "Default")
      (node (ref "L5") (pin "P$2") (pinfunction "2_P$2") (pintype "bidirectional"))
      (node (ref "U1") (pin "A2") (pinfunction "SIMOBUCK_SWSEL_A2") (pintype "bidirectional"))
    )
    (net (code "93") (name "Net-(LS1-N)") (class "Default")
      (node (ref "D4") (pin "ANODE") (pinfunction "ANODE_ANODE") (pintype "bidirectional"))
      (node (ref "LS1") (pin "-") (pinfunction "N_-") (pintype "passive"))
      (node (ref "Q2") (pin "D") (pinfunction "D_D") (pintype "passive"))
    )
    (net (code "94") (name "Net-(R6-Pad1)") (class "Default")
      (node (ref "R6") (pin "1") (pinfunction "1_1") (pintype "passive"))
      (node (ref "R7") (pin "2") (pinfunction "2_2") (pintype "passive"))
    )
    (net (code "95") (name "Net-(R8-Pad2)") (class "Default")
      (node (ref "R8") (pin "2") (pinfunction "2_2") (pintype "passive"))
      (node (ref "R9") (pin "1") (pinfunction "1_1") (pintype "passive"))
    )
    (net (code "96") (name "Net-(R10-Pad2)") (class "Default")
      (node (ref "R10") (pin "2") (pinfunction "2_2") (pintype "passive"))
      (node (ref "RT1") (pin "1") (pinfunction "1_1") (pintype "passive"))
    )
    (net (code "97") (name "Net-(R17-Pad1)") (class "Default")
      (node (ref "R17") (pin "1") (pinfunction "1_1") (pintype "passive"))
      (node (ref "R18") (pin "2") (pinfunction "2_2") (pintype "passive"))
    )
    (net (code "98") (name "Net-(RX1-Pad2)") (class "Default")
      (node (ref "RX1") (pin "2") (pinfunction "2_2") (pintype "passive"))
      (node (ref "SJ1") (pin "1") (pinfunction "1_1") (pintype "passive"))
    )
    (net (code "99") (name "Net-(S3A-OUT)") (class "Default")
      (node (ref "C37") (pin "1") (pinfunction "1_1") (pintype "bidirectional"))
      (node (ref "RZ2") (pin "1") (pinfunction "1_1") (pintype "passive"))
      (node (ref "S3") (pin "8") (pinfunction "OUT_8") (pintype "bidirectional"))
    )
    (net (code "100") (name "Net-(S3B-OUT)") (class "Default")
      (node (ref "C29") (pin "1") (pinfunction "1_1") (pintype "bidirectional"))
      (node (ref "RZ3") (pin "1") (pinfunction "1_1") (pintype "passive"))
      (node (ref "S3") (pin "5") (pinfunction "OUT_5") (pintype "bidirectional"))
    )
    (net (code "101") (name "Net-(TP0-TESTPOINT)") (class "Default")
      (node (ref "TP0") (pin "P$1") (pinfunction "TESTPOINT_P$1") (pintype "bidirectional"))
      (node (ref "U2") (pin "C2") (pinfunction "GPIO0/RXOKLED_C2") (pintype "bidirectional"))
    )
    (net (code "102") (name "Net-(TP1-TESTPOINT)") (class "Default")
      (node (ref "TP1") (pin "P$1") (pinfunction "TESTPOINT_P$1") (pintype "bidirectional"))
      (node (ref "U2") (pin "D3") (pinfunction "GPIO1/SFDLED_D3") (pintype "bidirectional"))
    )
    (net (code "103") (name "Net-(TP2-TESTPOINT)") (class "Default")
      (node (ref "TP2") (pin "P$1") (pinfunction "TESTPOINT_P$1") (pintype "bidirectional"))
      (node (ref "U2") (pin "E4") (pinfunction "GPIO2/RXLED_E4") (pintype "bidirectional"))
    )
    (net (code "104") (name "Net-(TP3-TESTPOINT)") (class "Default")
      (node (ref "TP3") (pin "P$1") (pinfunction "TESTPOINT_P$1") (pintype "bidirectional"))
      (node (ref "U2") (pin "E2") (pinfunction "GPIO3/TXLED_E2") (pintype "bidirectional"))
    )
    (net (code "105") (name "Net-(TP4-TESTPOINT)") (class "Default")
      (node (ref "TP4") (pin "P$1") (pinfunction "TESTPOINT_P$1") (pintype "bidirectional"))
      (node (ref "U2") (pin "F1") (pinfunction "GPIO4/EXTPA_F1") (pintype "bidirectional"))
    )
    (net (code "106") (name "Net-(TP5-TESTPOINT)") (class "Default")
      (node (ref "TP5") (pin "P$1") (pinfunction "TESTPOINT_P$1") (pintype "bidirectional"))
      (node (ref "U2") (pin "D1") (pinfunction "GPIO5/EXTTXE/SPIPOL_D1") (pintype "bidirectional"))
    )
    (net (code "107") (name "Net-(U1-RFIOP)") (class "Default")
      (node (ref "L7") (pin "1") (pinfunction "1_1") (pintype "passive"))
      (node (ref "U1") (pin "M2") (pinfunction "RFIOP_M2") (pintype "bidirectional"))
    )
    (net (code "108") (name "Net-(U1-VDDBH_SW--BLE_BUCK_SW)") (class "Default")
      (node (ref "L6") (pin "1") (pinfunction "1_1") (pintype "bidirectional"))
      (node (ref "U1") (pin "H12") (pinfunction "VDDBH_SW--BLE_BUCK_SW_H12") (pintype "bidirectional"))
    )
    (net (code "109") (name "Net-(U1-XI)") (class "Default")
      (node (ref "C8") (pin "1") (pinfunction "1_1") (pintype "passive"))
      (node (ref "U1") (pin "A4") (pinfunction "XI_A4") (pintype "bidirectional"))
      (node (ref "X3") (pin "2") (pinfunction "2_2") (pintype "bidirectional"))
    )
    (net (code "110") (name "Net-(U1-XI32M)") (class "Default")
      (node (ref "CX2") (pin "1") (pinfunction "1_1") (pintype "passive"))
      (node (ref "U1") (pin "C12") (pinfunction "XI32M_C12") (pintype "bidirectional"))
      (node (ref "X1") (pin "3") (pinfunction "2_3") (pintype "bidirectional"))
    )
    (net (code "111") (name "Net-(U1-XO)") (class "Default")
      (node (ref "C7") (pin "1") (pinfunction "1_1") (pintype "passive"))
      (node (ref "U1") (pin "A5") (pinfunction "XO_A5") (pintype "bidirectional"))
      (node (ref "X3") (pin "1") (pinfunction "1_1") (pintype "bidirectional"))
    )
    (net (code "112") (name "Net-(U1-XO32M)") (class "Default")
      (node (ref "CX1") (pin "1") (pinfunction "1_1") (pintype "passive"))
      (node (ref "U1") (pin "D12") (pinfunction "XO32M_D12") (pintype "bidirectional"))
      (node (ref "X1") (pin "1") (pinfunction "1_1") (pintype "bidirectional"))
    )
    (net (code "113") (name "Net-(U2-RF2)") (class "Default")
      (node (ref "R1") (pin "1") (pinfunction "1_1") (pintype "passive"))
      (node (ref "U2") (pin "H5") (pinfunction "RF2_H5") (pintype "bidirectional"))
    )
    (net (code "114") (name "Net-(U2-VDD2A)") (class "Default")
      (node (ref "C14") (pin "P$1") (pinfunction "P$1_P$1") (pintype "bidirectional"))
      (node (ref "FB1") (pin "P$2") (pinfunction "P$2_P$2") (pintype "bidirectional"))
      (node (ref "U2") (pin "F15") (pinfunction "VDD2A_F15") (pintype "bidirectional"))
    )
    (net (code "115") (name "Net-(U2-VIO_D)") (class "Default")
      (node (ref "C27") (pin "1") (pinfunction "1_1") (pintype "bidirectional"))
      (node (ref "U2") (pin "A4") (pinfunction "VIO_D_A4") (pintype "bidirectional"))
    )
    (net (code "116") (name "Net-(U2-VTX_D)") (class "Default")
      (node (ref "C41") (pin "P$2") (pinfunction "P$2_P$2") (pintype "bidirectional"))
      (node (ref "U2") (pin "C14") (pinfunction "VTX_D_C14") (pintype "bidirectional"))
    )
    (net (code "117") (name "Net-(U2-XTI)") (class "Default")
      (node (ref "C3") (pin "P$1") (pinfunction "P$1_P$1") (pintype "bidirectional"))
      (node (ref "U2") (pin "H15") (pinfunction "XTI_H15") (pintype "bidirectional"))
      (node (ref "X4") (pin "1") (pinfunction "1_1") (pintype "bidirectional"))
    )
    (net (code "118") (name "Net-(U2-XTO)") (class "Default")
      (node (ref "C4") (pin "P$1") (pinfunction "P$1_P$1") (pintype "bidirectional"))
      (node (ref "U2") (pin "G14") (pinfunction "XTO_G14") (pintype "bidirectional"))
      (node (ref "X4") (pin "3") (pinfunction "2_3") (pintype "bidirectional"))
    )
    (net (code "119") (name "Net-(U3-ISET)") (class "Default")
      (node (ref "R11") (pin "2") (pinfunction "2_2") (pintype "passive"))
      (node (ref "U3") (pin "2") (pinfunction "ISET_2") (pintype "bidirectional"))
    )
    (net (code "120") (name "Net-(U3-PRETERM)") (class "Default")
      (node (ref "RX2") (pin "2") (pinfunction "2_2") (pintype "passive"))
      (node (ref "U3") (pin "4") (pinfunction "PRETERM_4") (pintype "bidirectional"))
    )
    (net (code "121") (name "Net-(U4-AC1)") (class "Default")
      (node (ref "C12") (pin "1") (pinfunction "1_1") (pintype "bidirectional"))
      (node (ref "C13") (pin "1") (pinfunction "1_1") (pintype "bidirectional"))
      (node (ref "C18") (pin "2") (pinfunction "2_2") (pintype "bidirectional"))
      (node (ref "C20") (pin "1") (pinfunction "1_1") (pintype "bidirectional"))
      (node (ref "C21") (pin "1") (pinfunction "1_1") (pintype "bidirectional"))
      (node (ref "C22") (pin "1") (pinfunction "1_1") (pintype "bidirectional"))
      (node (ref "C23") (pin "2") (pinfunction "2_2") (pintype "bidirectional"))
      (node (ref "C42") (pin "2") (pinfunction "2_2") (pintype "bidirectional"))
      (node (ref "U4") (pin "2") (pinfunction "AC1_2") (pintype "bidirectional"))
    )
    (net (code "122") (name "Net-(U4-BOOT1)") (class "Default")
      (node (ref "C18") (pin "1") (pinfunction "1_1") (pintype "bidirectional"))
      (node (ref "U4") (pin "3") (pinfunction "BOOT1_3") (pintype "bidirectional"))
    )
    (net (code "123") (name "Net-(U4-BOOT2)") (class "Default")
      (node (ref "C19") (pin "1") (pinfunction "1_1") (pintype "bidirectional"))
      (node (ref "U4") (pin "17") (pinfunction "BOOT2_17") (pintype "bidirectional"))
    )
    (net (code "124") (name "Net-(U4-CLAMP1)") (class "Default")
      (node (ref "C42") (pin "1") (pinfunction "1_1") (pintype "bidirectional"))
      (node (ref "U4") (pin "5") (pinfunction "CLAMP1_5") (pintype "bidirectional"))
    )
    (net (code "125") (name "Net-(U4-CLAMP2)") (class "Default")
      (node (ref "C43") (pin "1") (pinfunction "1_1") (pintype "bidirectional"))
      (node (ref "U4") (pin "16") (pinfunction "CLAMP2_16") (pintype "bidirectional"))
    )
    (net (code "126") (name "Net-(U4-COMM1)") (class "Default")
      (node (ref "C23") (pin "1") (pinfunction "1_1") (pintype "bidirectional"))
      (node (ref "U4") (pin "6") (pinfunction "COMM1_6") (pintype "bidirectional"))
    )
    (net (code "127") (name "Net-(U4-COMM2)") (class "Default")
      (node (ref "C24") (pin "1") (pinfunction "1_1") (pintype "bidirectional"))
      (node (ref "U4") (pin "15") (pinfunction "COMM2_15") (pintype "bidirectional"))
    )
    (net (code "128") (name "Net-(U4-FOD)") (class "Default")
      (node (ref "R17") (pin "2") (pinfunction "2_2") (pintype "passive"))
      (node (ref "R7") (pin "1") (pinfunction "1_1") (pintype "passive"))
      (node (ref "R9") (pin "2") (pinfunction "2_2") (pintype "passive"))
      (node (ref "U4") (pin "14") (pinfunction "FOD_14") (pintype "bidirectional"))
    )
    (net (code "129") (name "Net-(U4-ILIM)") (class "Default")
      (node (ref "R8") (pin "1") (pinfunction "1_1") (pintype "passive"))
      (node (ref "U4") (pin "12") (pinfunction "ILIM_12") (pintype "bidirectional"))
    )
    (net (code "130") (name "Net-(U4-RECT)") (class "Default")
      (node (ref "C32") (pin "1") (pinfunction "1_1") (pintype "bidirectional"))
      (node (ref "C83") (pin "1") (pinfunction "1_1") (pintype "bidirectional"))
      (node (ref "C84") (pin "1") (pinfunction "1_1") (pintype "bidirectional"))
      (node (ref "R18") (pin "1") (pinfunction "1_1") (pintype "passive"))
      (node (ref "U4") (pin "18") (pinfunction "RECT_18") (pintype "bidirectional"))
    )
    (net (code "131") (name "Net-(U6-CAP)") (class "Default")
      (node (ref "C40") (pin "1") (pinfunction "1_1") (pintype "bidirectional"))
      (node (ref "U6") (pin "9") (pinfunction "CAP_9") (pintype "bidirectional"))
    )
    (net (code "132") (name "Net-(U6-PS1)") (class "Default")
      (node (ref "SJ4") (pin "2") (pinfunction "2_2") (pintype "passive"))
      (node (ref "U6") (pin "5") (pinfunction "PS1_5") (pintype "input"))
    )
    (net (code "133") (name "Net-(U7-VCTRL)") (class "Default")
      (node (ref "SJ3") (pin "2") (pinfunction "2_2") (pintype "passive"))
      (node (ref "U7") (pin "8") (pinfunction "VCTRL_8") (pintype "bidirectional"))
    )
    (net (code "134") (name "RF1") (class "Default")
      (node (ref "A1") (pin "FEED") (pinfunction "ANTENNA_FEED") (pintype "bidirectional"))
      (node (ref "S2") (pin "9") (pinfunction "J2_9") (pintype "bidirectional"))
    )
    (net (code "135") (name "RF2") (class "Default")
      (node (ref "A2") (pin "FEED") (pinfunction "ANTENNA_FEED") (pintype "bidirectional"))
      (node (ref "S2") (pin "3") (pinfunction "J3_3") (pintype "bidirectional"))
    )
    (net (code "136") (name "RF3") (class "Default")
      (node (ref "A3") (pin "FEED") (pinfunction "ANTENNA_FEED") (pintype "bidirectional"))
      (node (ref "S2") (pin "1") (pinfunction "J1_1") (pintype "bidirectional"))
    )
    (net (code "137") (name "RFC") (class "Default")
      (node (ref "S2") (pin "11") (pinfunction "RFC_11") (pintype "bidirectional"))
      (node (ref "U7") (pin "2") (pinfunction "LNA_IN_2") (pintype "bidirectional"))
    )
    (net (code "138") (name "VBAT") (class "Default")
      (node (ref "C61") (pin "P$2") (pinfunction "2_P$2") (pintype "bidirectional"))
      (node (ref "J3") (pin "1") (pinfunction "1_1") (pintype "passive"))
      (node (ref "J4") (pin "3") (pinfunction "3_3") (pintype "bidirectional"))
      (node (ref "J4") (pin "3SUPP") (pinfunction "3_3SUPP") (pintype "bidirectional"))
      (node (ref "S1") (pin "2") (pinfunction "2_2") (pintype "passive"))
      (node (ref "U3") (pin "10") (pinfunction "OUT_10") (pintype "bidirectional"))
    )
    (net (code "139") (name "VBAT_SWITCHED") (class "Default")
      (node (ref "C51") (pin "P$1") (pinfunction "1_P$1") (pintype "bidirectional"))
      (node (ref "C57") (pin "P$1") (pinfunction "1_P$1") (pintype "bidirectional"))
      (node (ref "C76") (pin "2") (pinfunction "2_2") (pintype "bidirectional"))
      (node (ref "C79") (pin "1") (pinfunction "1_1") (pintype "bidirectional"))
      (node (ref "R28") (pin "2") (pinfunction "2_2") (pintype "passive"))
      (node (ref "R29") (pin "1") (pinfunction "1_1") (pintype "passive"))
      (node (ref "R30") (pin "1") (pinfunction "1_1") (pintype "passive"))
      (node (ref "S1") (pin "3") (pinfunction "3_3") (pintype "passive"))
      (node (ref "VR1") (pin "1") (pinfunction "VIN2_1") (pintype "bidirectional"))
      (node (ref "VR1") (pin "7") (pinfunction "VIN1_7") (pintype "bidirectional"))
      (node (ref "VR4") (pin "4") (pinfunction "IN_4") (pintype "bidirectional"))
      (node (ref "VR5") (pin "1") (pinfunction "IN_1") (pintype "bidirectional"))
    )
    (net (code "140") (name "VDDAUDA_1P8-CLEAN") (class "Default")
      (node (ref "C48") (pin "P$1") (pinfunction "1_P$1") (pintype "bidirectional"))
      (node (ref "C68") (pin "P$1") (pinfunction "1_P$1") (pintype "bidirectional"))
      (node (ref "U1") (pin "B11") (pinfunction "VDDAUDA_B11") (pintype "bidirectional"))
      (node (ref "VR2") (pin "1") (pinfunction "OUT_1") (pintype "power_in"))
    )
    (net (code "141") (name "VQI") (class "Default")
      (node (ref "C33") (pin "1") (pinfunction "1_1") (pintype "bidirectional"))
      (node (ref "C60") (pin "P$2") (pinfunction "2_P$2") (pintype "bidirectional"))
      (node (ref "C82") (pin "1") (pinfunction "1_1") (pintype "bidirectional"))
      (node (ref "Q1") (pin "A2") (pinfunction "D1_A2") (pintype "bidirectional"))
      (node (ref "Q1") (pin "A3") (pinfunction "D1_A3") (pintype "bidirectional"))
      (node (ref "Q1") (pin "B3") (pinfunction "D1_B3") (pintype "bidirectional"))
      (node (ref "U3") (pin "1") (pinfunction "IN_1") (pintype "bidirectional"))
      (node (ref "U4") (pin "4") (pinfunction "OUT_4") (pintype "bidirectional"))
    )
    (net (code "142") (name "VR1_1P8_EN") (class "Default")
      (node (ref "R30") (pin "2") (pinfunction "2_2") (pintype "passive"))
      (node (ref "VR1") (pin "6") (pinfunction "EN1_6") (pintype "bidirectional"))
    )
    (net (code "143") (name "VR1_2P5_EN") (class "Default")
      (node (ref "R29") (pin "2") (pinfunction "2_2") (pintype "passive"))
      (node (ref "VR1") (pin "12") (pinfunction "EN2_12") (pintype "bidirectional"))
    )
    (net (code "144") (name "VUSB") (class "Default")
      (node (ref "C59") (pin "P$1") (pinfunction "1_P$1") (pintype "bidirectional"))
      (node (ref "D5") (pin "4") (pinfunction "VCC_4") (pintype "bidirectional"))
      (node (ref "J7") (pin "A4/B9") (pinfunction "VBUS_A4/B9") (pintype "power_in"))
      (node (ref "J7") (pin "B4/A9") (pinfunction "VBUS_B4/A9") (pintype "power_in"))
      (node (ref "Q1") (pin "B2") (pinfunction "D2_B2") (pintype "bidirectional"))
      (node (ref "Q1") (pin "C2") (pinfunction "D2_C2") (pintype "bidirectional"))
      (node (ref "Q1") (pin "C3") (pinfunction "D2_C3") (pintype "bidirectional"))
      (node (ref "R26") (pin "2") (pinfunction "2_2") (pintype "passive"))
      (node (ref "U4") (pin "9") (pinfunction "AD_9") (pintype "bidirectional"))
    )
    (net (code "145") (name "unconnected-(J7-SBU1-PadA8)") (class "Default")
      (node (ref "J7") (pin "A8") (pinfunction "SBU1_A8") (pintype "bidirectional"))
    )
    (net (code "146") (name "unconnected-(J7-SBU2-PadB8)") (class "Default")
      (node (ref "J7") (pin "B8") (pinfunction "SBU2_B8") (pintype "bidirectional"))
    )
    (net (code "147") (name "unconnected-(Q1-S-PadB1)") (class "Default")
      (node (ref "Q1") (pin "B1") (pinfunction "S_B1") (pintype "bidirectional"))
    )
    (net (code "148") (name "unconnected-(S1-Pad1)") (class "Default")
      (node (ref "S1") (pin "1") (pinfunction "1_1") (pintype "passive"))
    )
    (net (code "149") (name "unconnected-(U1-GPIO0-PadH3)") (class "Default")
      (node (ref "U1") (pin "H3") (pinfunction "GPIO0_H3") (pintype "bidirectional"))
    )
    (net (code "150") (name "unconnected-(U1-GPIO1-PadJ4)") (class "Default")
      (node (ref "U1") (pin "J4") (pinfunction "GPIO1_J4") (pintype "bidirectional"))
    )
    (net (code "151") (name "unconnected-(U1-GPIO2-PadK4)") (class "Default")
      (node (ref "U1") (pin "K4") (pinfunction "GPIO2_K4") (pintype "bidirectional"))
    )
    (net (code "152") (name "unconnected-(U1-GPIO4-PadM4)") (class "Default")
      (node (ref "U1") (pin "M4") (pinfunction "GPIO4_M4") (pintype "bidirectional"))
    )
    (net (code "153") (name "unconnected-(U1-GPIO5-PadH4)") (class "Default")
      (node (ref "U1") (pin "H4") (pinfunction "GPIO5_H4") (pintype "bidirectional"))
    )
    (net (code "154") (name "unconnected-(U1-GPIO7-PadJ6)") (class "Default")
      (node (ref "U1") (pin "J6") (pinfunction "GPIO7_J6") (pintype "bidirectional"))
    )
    (net (code "155") (name "unconnected-(U1-GPIO11-PadE4)") (class "Default")
      (node (ref "U1") (pin "E4") (pinfunction "GPIO11_E4") (pintype "bidirectional"))
    )
    (net (code "156") (name "unconnected-(U1-GPIO12-PadB4)") (class "Default")
      (node (ref "U1") (pin "B4") (pinfunction "GPIO12_B4") (pintype "bidirectional"))
    )
    (net (code "157") (name "unconnected-(U1-GPIO15-PadE5)") (class "Default")
      (node (ref "U1") (pin "E5") (pinfunction "GPIO15_E5") (pintype "bidirectional"))
    )
    (net (code "158") (name "unconnected-(U1-GPIO16-PadD7)") (class "Default")
      (node (ref "U1") (pin "D7") (pinfunction "GPIO16_D7") (pintype "bidirectional"))
    )
    (net (code "159") (name "unconnected-(U1-GPIO19-PadC3)") (class "Default")
      (node (ref "U1") (pin "C3") (pinfunction "GPIO19_C3") (pintype "bidirectional"))
    )
    (net (code "160") (name "unconnected-(U1-GPIO22-PadF3)") (class "Default")
      (node (ref "U1") (pin "F3") (pinfunction "GPIO22_F3") (pintype "bidirectional"))
    )
    (net (code "161") (name "unconnected-(U1-GPIO23-PadF2)") (class "Default")
      (node (ref "U1") (pin "F2") (pinfunction "GPIO23_F2") (pintype "bidirectional"))
    )
    (net (code "162") (name "unconnected-(U1-GPIO28-PadE3)") (class "Default")
      (node (ref "U1") (pin "E3") (pinfunction "GPIO28_E3") (pintype "bidirectional"))
    )
    (net (code "163") (name "unconnected-(U1-GPIO29-PadF4)") (class "Default")
      (node (ref "U1") (pin "F4") (pinfunction "GPIO29_F4") (pintype "bidirectional"))
    )
    (net (code "164") (name "unconnected-(U1-GPIO37-PadF11)") (class "Default")
      (node (ref "U1") (pin "F11") (pinfunction "GPIO37_F11") (pintype "bidirectional"))
    )
    (net (code "165") (name "unconnected-(U1-GPIO38-PadF12)") (class "Default")
      (node (ref "U1") (pin "F12") (pinfunction "GPIO38_F12") (pintype "bidirectional"))
    )
    (net (code "166") (name "unconnected-(U1-GPIO52-PadC10)") (class "Default")
      (node (ref "U1") (pin "C10") (pinfunction "GPIO52_C10") (pintype "bidirectional"))
    )
    (net (code "167") (name "unconnected-(U1-GPIO54-PadD10)") (class "Default")
      (node (ref "U1") (pin "D10") (pinfunction "GPIO54_D10") (pintype "bidirectional"))
    )
    (net (code "168") (name "unconnected-(U1-GPIO56-PadE10)") (class "Default")
      (node (ref "U1") (pin "E10") (pinfunction "GPIO56_E10") (pintype "bidirectional"))
    )
    (net (code "169") (name "unconnected-(U1-GPIO57-PadE9)") (class "Default")
      (node (ref "U1") (pin "E9") (pinfunction "GPIO57_E9") (pintype "bidirectional"))
    )
    (net (code "170") (name "unconnected-(U1-GPIO59-PadJ8)") (class "Default")
      (node (ref "U1") (pin "J8") (pinfunction "GPIO59_J8") (pintype "bidirectional"))
    )
    (net (code "171") (name "unconnected-(U1-GPIO61-PadK6)") (class "Default")
      (node (ref "U1") (pin "K6") (pinfunction "GPIO61_K6") (pintype "bidirectional"))
    )
    (net (code "172") (name "unconnected-(U1-GPIO62-PadL6)") (class "Default")
      (node (ref "U1") (pin "L6") (pinfunction "GPIO62_L6") (pintype "bidirectional"))
    )
    (net (code "173") (name "unconnected-(U1-GPIO64-PadB6)") (class "Default")
      (node (ref "U1") (pin "B6") (pinfunction "GPIO64_B6") (pintype "bidirectional"))
    )
    (net (code "174") (name "unconnected-(U1-GPIO67-PadC6)") (class "Default")
      (node (ref "U1") (pin "C6") (pinfunction "GPIO67_C6") (pintype "bidirectional"))
    )
    (net (code "175") (name "unconnected-(U1-GPIO68-PadB7)") (class "Default")
      (node (ref "U1") (pin "B7") (pinfunction "GPIO68_B7") (pintype "bidirectional"))
    )
    (net (code "176") (name "unconnected-(U1-GPIO70-PadC5)") (class "Default")
      (node (ref "U1") (pin "C5") (pinfunction "GPIO70_C5") (pintype "bidirectional"))
    )
    (net (code "177") (name "unconnected-(U1-GPIO71-PadC7)") (class "Default")
      (node (ref "U1") (pin "C7") (pinfunction "GPIO71_C7") (pintype "bidirectional"))
    )
    (net (code "178") (name "unconnected-(U1-GPIO73-PadD8)") (class "Default")
      (node (ref "U1") (pin "D8") (pinfunction "GPIO73_D8") (pintype "bidirectional"))
    )
    (net (code "179") (name "unconnected-(U1-GPIO74-PadG11)") (class "Default")
      (node (ref "U1") (pin "G11") (pinfunction "GPIO74_G11") (pintype "bidirectional"))
    )
    (net (code "180") (name "unconnected-(U1-GPIO75-PadH11)") (class "Default")
      (node (ref "U1") (pin "H11") (pinfunction "GPIO75_H11") (pintype "bidirectional"))
    )
    (net (code "181") (name "unconnected-(U1-GPIO76-PadJ11)") (class "Default")
      (node (ref "U1") (pin "J11") (pinfunction "GPIO76_J11") (pintype "bidirectional"))
    )
    (net (code "182") (name "unconnected-(U1-GPIO77-PadK11)") (class "Default")
      (node (ref "U1") (pin "K11") (pinfunction "GPIO77_K11") (pintype "bidirectional"))
    )
    (net (code "183") (name "unconnected-(U1-GPIO82-PadL9)") (class "Default")
      (node (ref "U1") (pin "L9") (pinfunction "GPIO82_L9") (pintype "bidirectional"))
    )
    (net (code "184") (name "unconnected-(U1-GPIO83-PadK9)") (class "Default")
      (node (ref "U1") (pin "K9") (pinfunction "GPIO83_K9") (pintype "bidirectional"))
    )
    (net (code "185") (name "unconnected-(U1-GPIO84-PadJ9)") (class "Default")
      (node (ref "U1") (pin "J9") (pinfunction "GPIO84_J9") (pintype "bidirectional"))
    )
    (net (code "186") (name "unconnected-(U1-GPIO85-PadH9)") (class "Default")
      (node (ref "U1") (pin "H9") (pinfunction "GPIO85_H9") (pintype "bidirectional"))
    )
    (net (code "187") (name "unconnected-(U1-GPIO86-PadG10)") (class "Default")
      (node (ref "U1") (pin "G10") (pinfunction "GPIO86_G10") (pintype "bidirectional"))
    )
    (net (code "188") (name "unconnected-(U1-GPIO87-PadG9)") (class "Default")
      (node (ref "U1") (pin "G9") (pinfunction "GPIO87_G9") (pintype "bidirectional"))
    )
    (net (code "189") (name "unconnected-(U1-GPIO89-PadF10)") (class "Default")
      (node (ref "U1") (pin "F10") (pinfunction "GPIO89_F10") (pintype "bidirectional"))
    )
    (net (code "190") (name "unconnected-(U1-GPIO90-PadJ2)") (class "Default")
      (node (ref "U1") (pin "J2") (pinfunction "GPIO90_J2") (pintype "bidirectional"))
    )
    (net (code "191") (name "unconnected-(U1-GPIO91-PadK2)") (class "Default")
      (node (ref "U1") (pin "K2") (pinfunction "GPIO91_K2") (pintype "bidirectional"))
    )
    (net (code "192") (name "unconnected-(U1-LPADC_D0NSE0-PadA10)") (class "Default")
      (node (ref "U1") (pin "A10") (pinfunction "LPADC_D0NSE0_A10") (pintype "input"))
    )
    (net (code "193") (name "unconnected-(U1-LPADC_D0PSE1-PadA11)") (class "Default")
      (node (ref "U1") (pin "A11") (pinfunction "LPADC_D0PSE1_A11") (pintype "input"))
    )
    (net (code "194") (name "unconnected-(U1-LPADC_D1NSE2-PadC11)") (class "Default")
      (node (ref "U1") (pin "C11") (pinfunction "LPADC_D1NSE2_C11") (pintype "input"))
    )
    (net (code "195") (name "unconnected-(U1-LPADC_D1PSE3-PadD11)") (class "Default")
      (node (ref "U1") (pin "D11") (pinfunction "LPADC_D1PSE3_D11") (pintype "input"))
    )
    (net (code "196") (name "unconnected-(U1-MIPI_CLKN-PadJ12)") (class "Default")
      (node (ref "U1") (pin "J12") (pinfunction "MIPI_CLKN_J12") (pintype "bidirectional"))
    )
    (net (code "197") (name "unconnected-(U1-MIPI_CLKP-PadK12)") (class "Default")
      (node (ref "U1") (pin "K12") (pinfunction "MIPI_CLKP_K12") (pintype "bidirectional"))
    )
    (net (code "198") (name "unconnected-(U1-MIPI_DON-PadL12)") (class "Default")
      (node (ref "U1") (pin "L12") (pinfunction "MIPI_DON_L12") (pintype "bidirectional"))
    )
    (net (code "199") (name "unconnected-(U1-MIPI_DOP-PadM12)") (class "Default")
      (node (ref "U1") (pin "M12") (pinfunction "MIPI_DOP_M12") (pintype "bidirectional"))
    )
    (net (code "200") (name "unconnected-(U1-TXEN-PadK1)") (class "Default")
      (node (ref "U1") (pin "K1") (pinfunction "TXEN_K1") (pintype "output"))
    )
    (net (code "201") (name "unconnected-(VR1-NC1-Pad5)") (class "Default")
      (node (ref "VR1") (pin "5") (pinfunction "NC1_5") (pintype "bidirectional"))
    )
    (net (code "202") (name "unconnected-(VR1-NC2-Pad11)") (class "Default")
      (node (ref "VR1") (pin "11") (pinfunction "NC2_11") (pintype "bidirectional"))
    )
    (net (code "203") (name "~{AD_EN}") (class "Default")
      (node (ref "Q1") (pin "A1") (pinfunction "G1_A1") (pintype "input"))
      (node (ref "Q1") (pin "C1") (pinfunction "G2_C1") (pintype "input"))
      (node (ref "U4") (pin "8") (pinfunction "~{AD-EN}_8") (pintype "bidirectional"))
    )
  )
)
